# stm32n657.net
KiCad netlist of a schematic drawn in Altium Designer
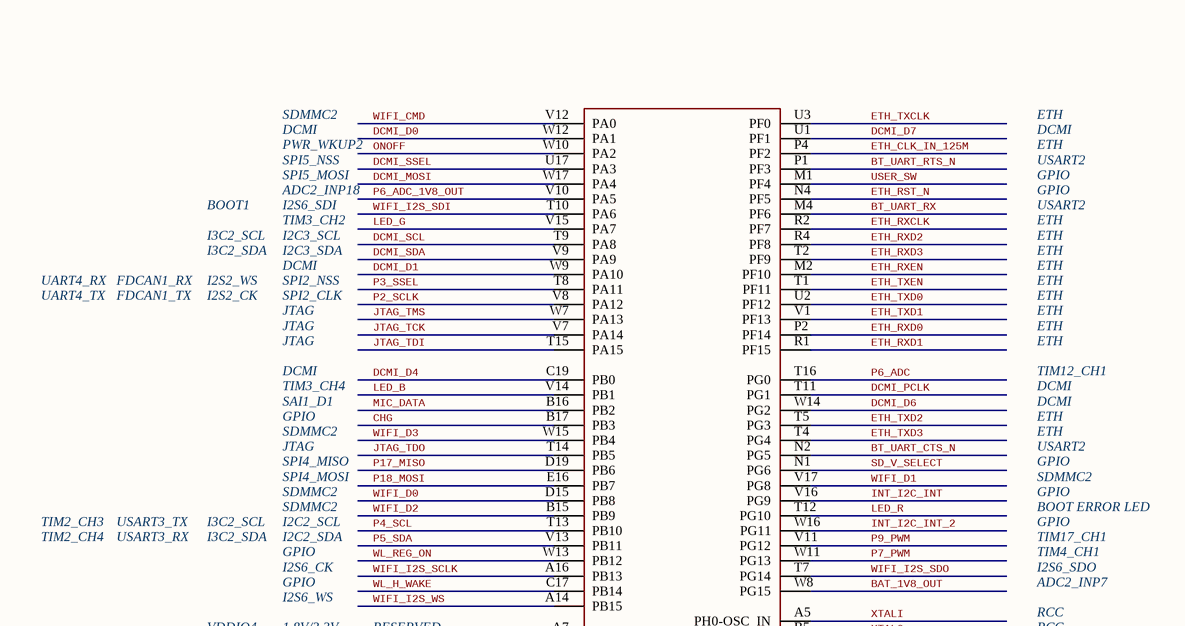
[diagram p0: stm32n657.SchDoc, top left]
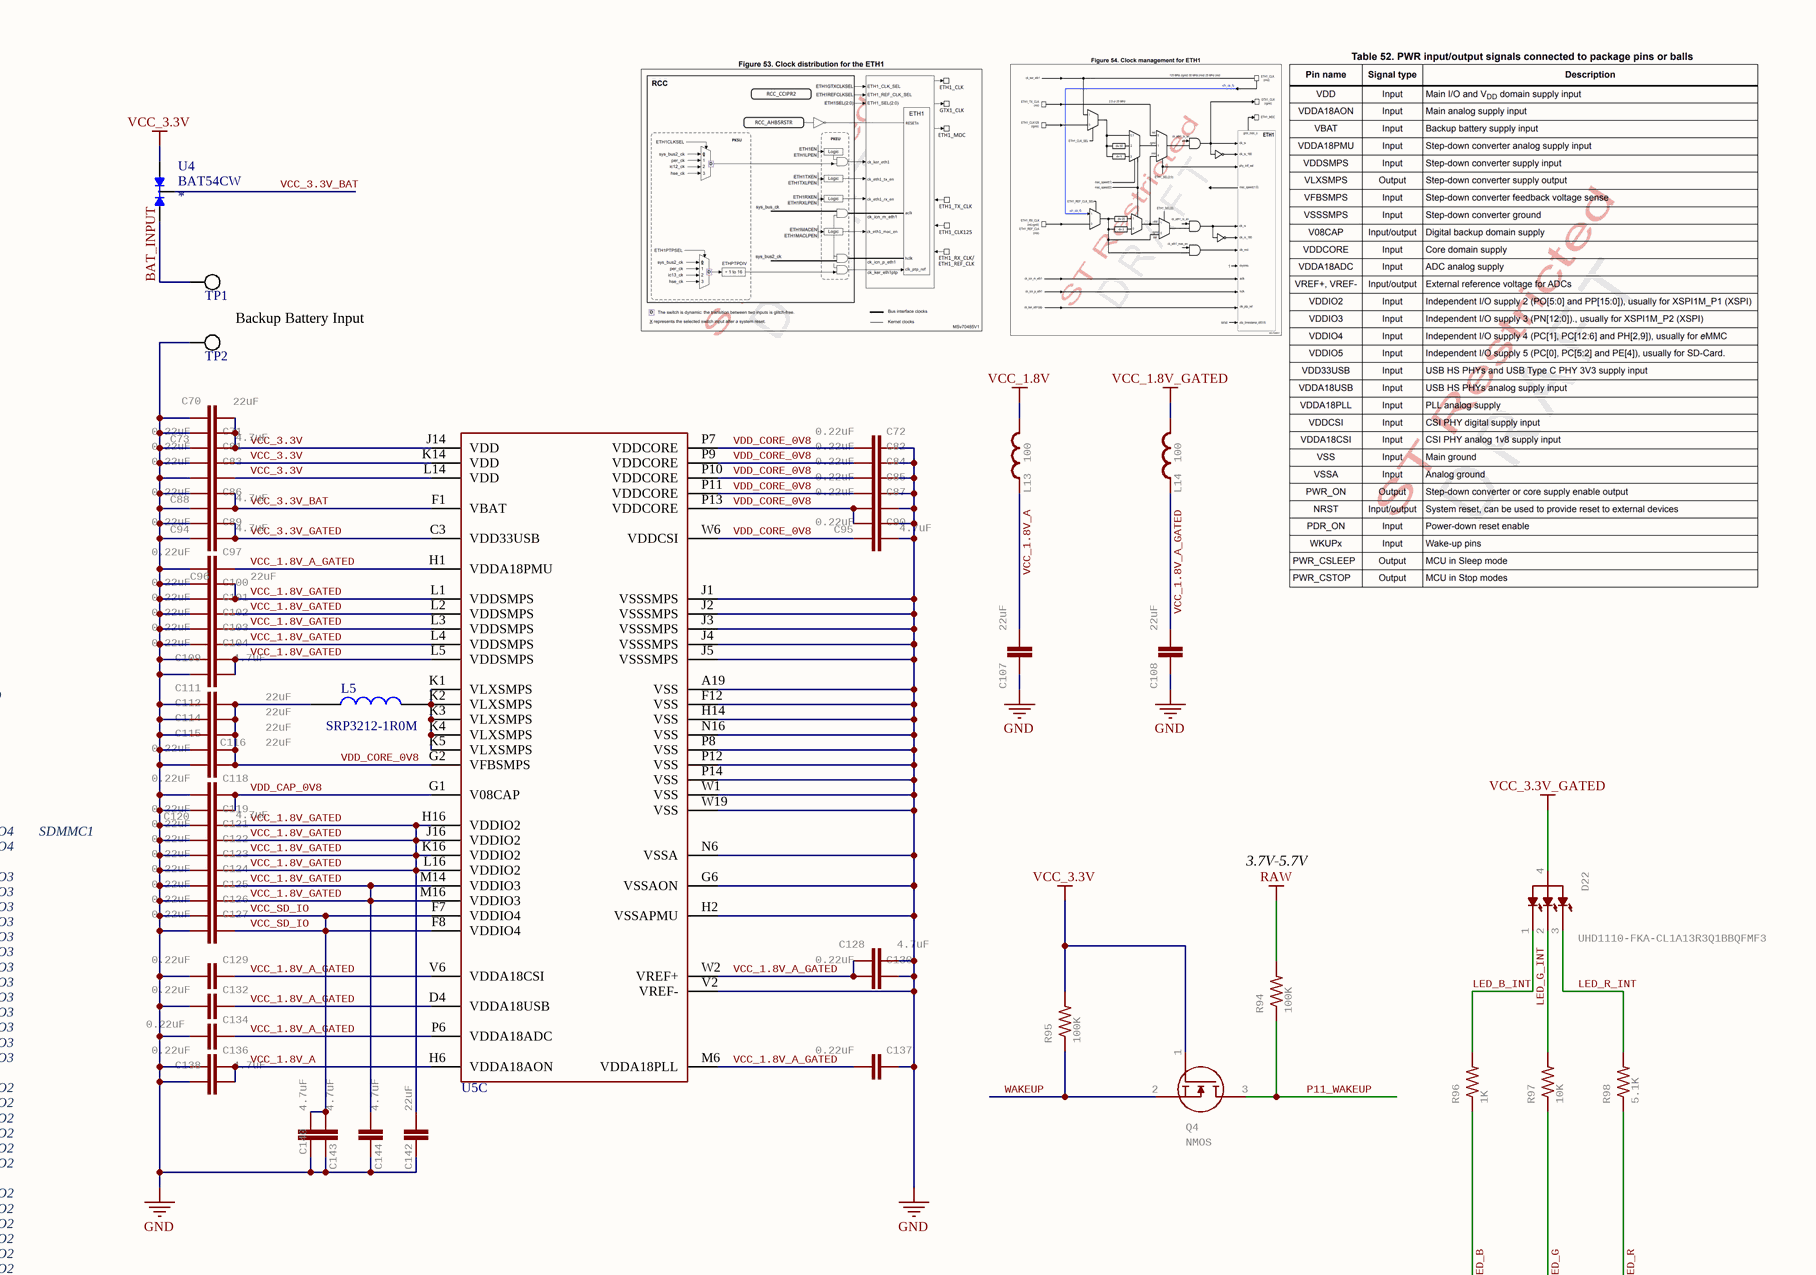
[diagram p1: stm32n657.SchDoc, top right]
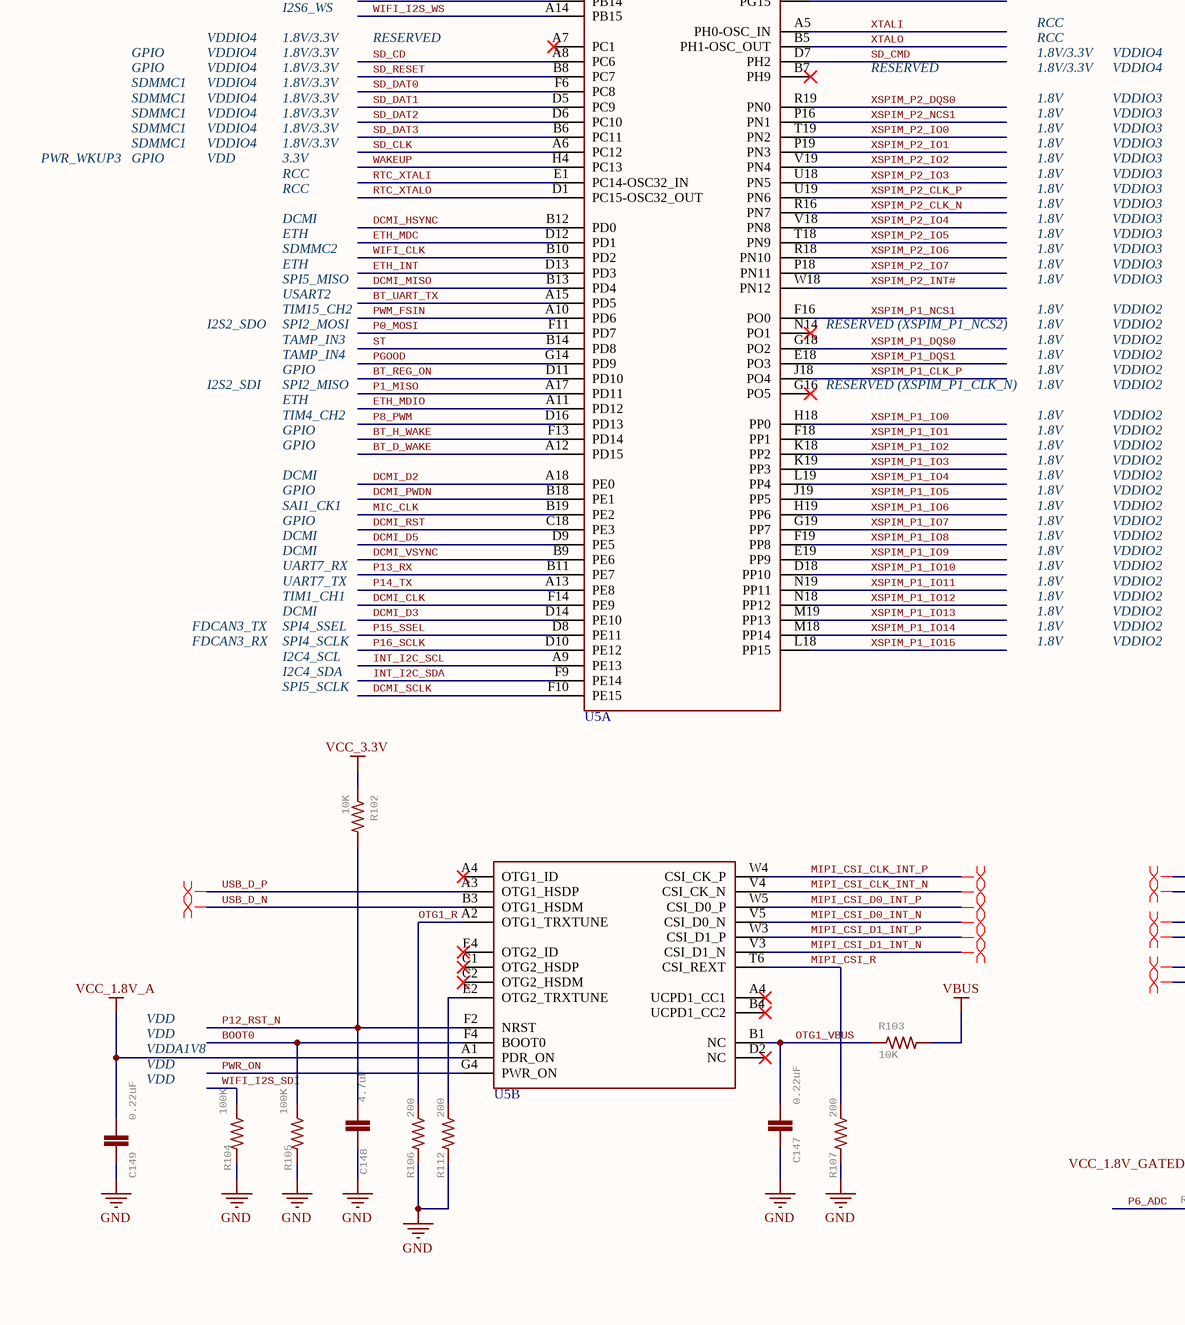
[diagram p2: stm32n657.SchDoc, bottom left]
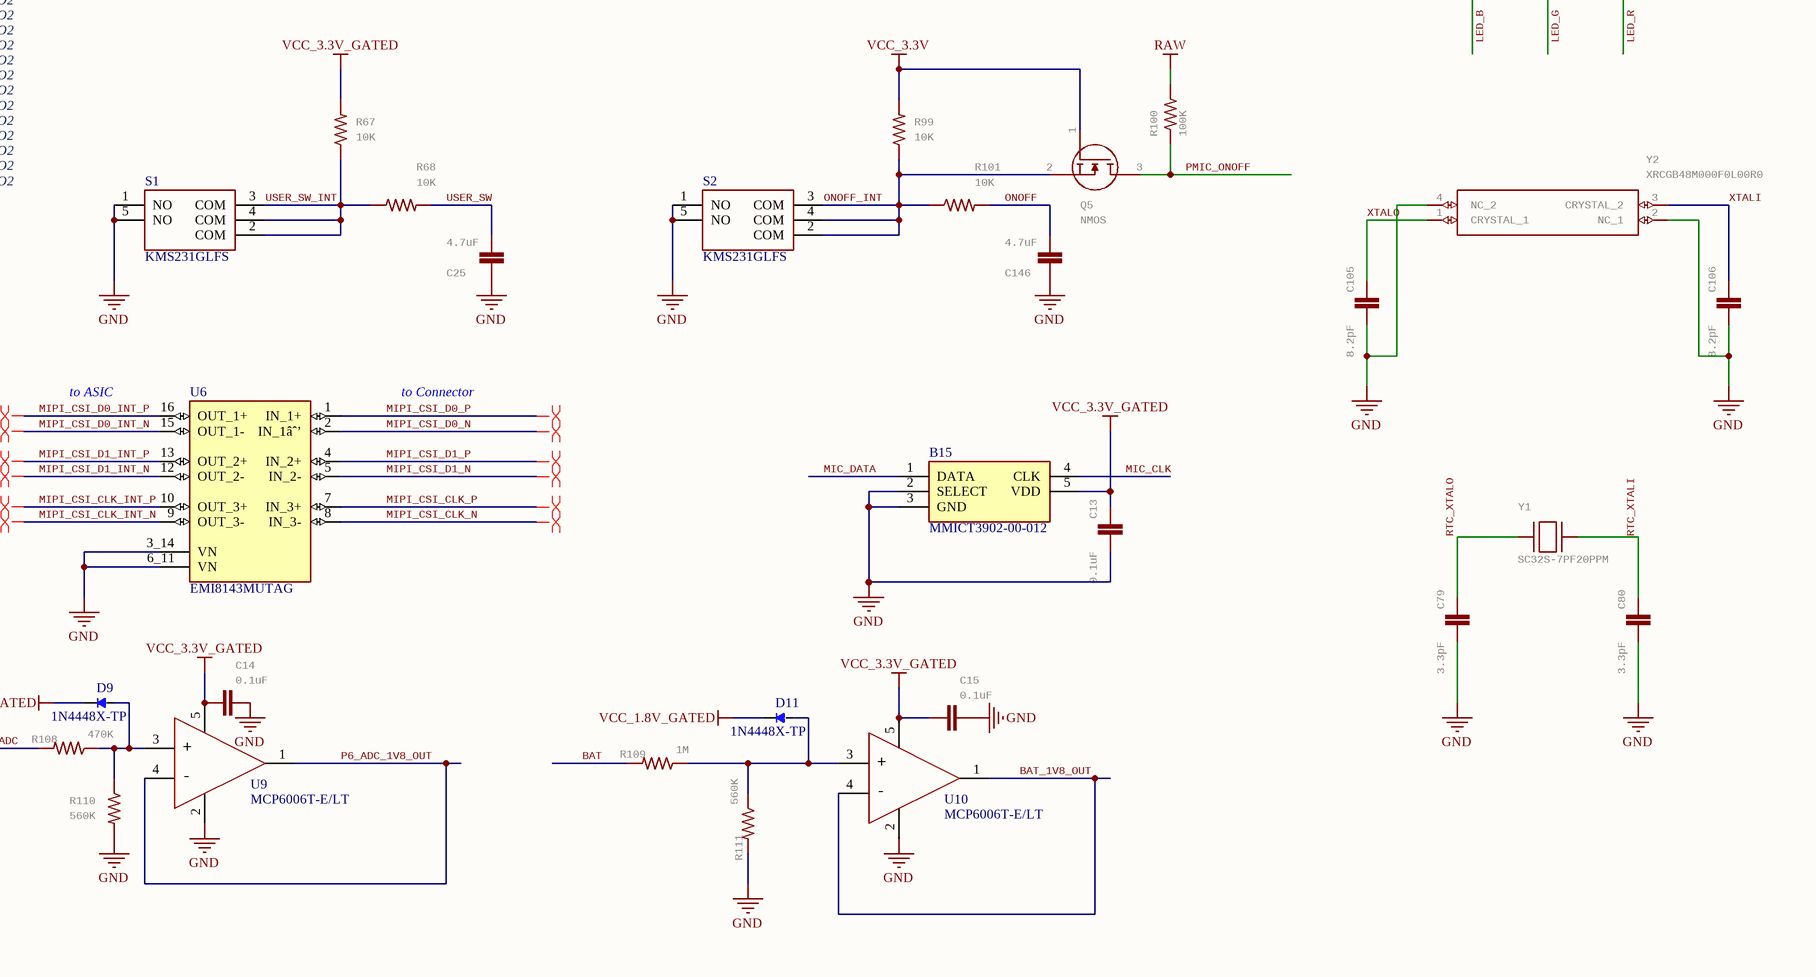
[diagram p3: stm32n657.SchDoc, bottom right]

(export (version "E")
  (design (tool "Eeschema 10.0.6"))
  (components
    (comp (ref "B15")
      (value "MMICT3902-00-012")
      (footprint "MMICT390200012")
      (description "Mic Omni-Directional -26dB Rectangle Solder Pad")
      (fields (field (name "MOUSER PART NUMBER") "410-MMICT3902-00-012"))
      (libsource (lib "MMICT3902-00-012") (part "MMICT3902-00-012"))
    )
    (comp (ref "C13")
      (value "0.1uF")
      (footprint "0402-CAP")
      (description "CAPACITOR, European symbol")
      (fields (field (name "MPN") "C0402C104Z4VAC"))
      (libsource (lib "") (part "C-EUC0201_1"))
    )
    (comp (ref "C14")
      (value "0.1uF")
      (footprint "0402-CAP")
      (description "CAPACITOR, European symbol")
      (fields (field (name "MPN") "C0402C104Z4VAC"))
      (libsource (lib "openmv-ae3") (part "C-EUC0201"))
    )
    (comp (ref "C15")
      (value "0.1uF")
      (footprint "0402-CAP")
      (description "CAPACITOR, European symbol")
      (fields (field (name "MPN") "C0402C104Z4VAC"))
      (libsource (lib "openmv-ae3") (part "C-EUC0201"))
    )
    (comp (ref "C25")
      (value "4.7uF")
      (footprint "0402-CAP")
      (description "CapacitorStandard 0603 ceramic capacitor, and 0.1\" leaded capacitor.")
      (fields (field (name "MPN") "JMK105BBJ475MV-F"))
      (libsource (lib "") (part "CAP0402-CAP_3"))
    )
    (comp (ref "C70")
      (value "22uF")
      (footprint "0805")
      (fields (field (name "MPN") "CL21A226MQQNNNE"))
      (libsource (lib "") (part "22UF-0805-6.3V-20%_1"))
    )
    (comp (ref "C71")
      (value "0.22uF")
      (footprint "C0201")
      (description "CAPACITOR, European symbol")
      (fields (field (name "MPN") "GRM033R60J224ME15D"))
      (libsource (lib "rt10") (part "C-EUC0201"))
    )
    (comp (ref "C72")
      (value "0.22uF")
      (footprint "C0201")
      (description "CAPACITOR, European symbol")
      (fields (field (name "MPN") "GRM033R60J224ME15D"))
      (libsource (lib "rt10") (part "C-EUC0201"))
    )
    (comp (ref "C73")
      (value "4.7uF")
      (footprint "0402-CAP")
      (description "CapacitorStandard 0603 ceramic capacitor, and 0.1\" leaded capacitor.")
      (fields (field (name "MPN") "JMK105BBJ475MV-F"))
      (libsource (lib "rt10") (part "CAP0402-CAP"))
    )
    (comp (ref "C79")
      (value "3.3pF")
      (footprint "C0201")
      (description "CAPACITOR, European symbol")
      (fields (field (name "MPN") "GRM0335C1H3R3CA01D"))
      (libsource (lib "") (part "C-EUC0201_1"))
    )
    (comp (ref "C80")
      (value "3.3pF")
      (footprint "C0201")
      (description "CAPACITOR, European symbol")
      (fields (field (name "MPN") "GRM0335C1H3R3CA01D"))
      (libsource (lib "") (part "C-EUC0201_1"))
    )
    (comp (ref "C81")
      (value "0.22uF")
      (footprint "C0201")
      (description "CAPACITOR, European symbol")
      (fields (field (name "MPN") "GRM033R60J224ME15D"))
      (libsource (lib "rt10") (part "C-EUC0201"))
    )
    (comp (ref "C82")
      (value "0.22uF")
      (footprint "C0201")
      (description "CAPACITOR, European symbol")
      (fields (field (name "MPN") "GRM033R60J224ME15D"))
      (libsource (lib "rt10") (part "C-EUC0201"))
    )
    (comp (ref "C83")
      (value "0.22uF")
      (footprint "C0201")
      (description "CAPACITOR, European symbol")
      (fields (field (name "MPN") "GRM033R60J224ME15D"))
      (libsource (lib "rt10") (part "C-EUC0201"))
    )
    (comp (ref "C84")
      (value "0.22uF")
      (footprint "C0201")
      (description "CAPACITOR, European symbol")
      (fields (field (name "MPN") "GRM033R60J224ME15D"))
      (libsource (lib "rt10") (part "C-EUC0201"))
    )
    (comp (ref "C85")
      (value "0.22uF")
      (footprint "C0201")
      (description "CAPACITOR, European symbol")
      (fields (field (name "MPN") "GRM033R60J224ME15D"))
      (libsource (lib "rt10") (part "C-EUC0201"))
    )
    (comp (ref "C86")
      (value "0.22uF")
      (footprint "C0201")
      (description "CAPACITOR, European symbol")
      (fields (field (name "MPN") "GRM033R60J224ME15D"))
      (libsource (lib "rt10") (part "C-EUC0201"))
    )
    (comp (ref "C87")
      (value "0.22uF")
      (footprint "C0201")
      (description "CAPACITOR, European symbol")
      (fields (field (name "MPN") "GRM033R60J224ME15D"))
      (libsource (lib "rt10") (part "C-EUC0201"))
    )
    (comp (ref "C88")
      (value "4.7uF")
      (footprint "0402-CAP")
      (description "CapacitorStandard 0603 ceramic capacitor, and 0.1\" leaded capacitor.")
      (fields (field (name "MPN") "JMK105BBJ475MV-F"))
      (libsource (lib "rt10") (part "CAP0402-CAP"))
    )
    (comp (ref "C89")
      (value "0.22uF")
      (footprint "C0201")
      (description "CAPACITOR, European symbol")
      (fields (field (name "MPN") "GRM033R60J224ME15D"))
      (libsource (lib "rt10") (part "C-EUC0201"))
    )
    (comp (ref "C90")
      (value "0.22uF")
      (footprint "C0201")
      (description "CAPACITOR, European symbol")
      (fields (field (name "MPN") "GRM033R60J224ME15D"))
      (libsource (lib "rt10") (part "C-EUC0201"))
    )
    (comp (ref "C94")
      (value "4.7uF")
      (footprint "0402-CAP")
      (description "CapacitorStandard 0603 ceramic capacitor, and 0.1\" leaded capacitor.")
      (fields (field (name "MPN") "JMK105BBJ475MV-F"))
      (libsource (lib "rt10") (part "CAP0402-CAP"))
    )
    (comp (ref "C95")
      (value "4.7uF")
      (footprint "0402-CAP")
      (description "CapacitorStandard 0603 ceramic capacitor, and 0.1\" leaded capacitor.")
      (fields (field (name "MPN") "JMK105BBJ475MV-F"))
      (libsource (lib "rt10") (part "CAP0402-CAP"))
    )
    (comp (ref "C96")
      (value "22uF")
      (footprint "0805")
      (fields (field (name "MPN") "CL21A226MQQNNNE"))
      (libsource (lib "") (part "22UF-0805-6.3V-20%_1"))
    )
    (comp (ref "C97")
      (value "0.22uF")
      (footprint "C0201")
      (description "CAPACITOR, European symbol")
      (fields (field (name "MPN") "GRM033R60J224ME15D"))
      (libsource (lib "rt10") (part "C-EUC0201"))
    )
    (comp (ref "C100")
      (value "0.22uF")
      (footprint "C0201")
      (description "CAPACITOR, European symbol")
      (fields (field (name "MPN") "GRM033R60J224ME15D"))
      (libsource (lib "rt10") (part "C-EUC0201"))
    )
    (comp (ref "C101")
      (value "0.22uF")
      (footprint "C0201")
      (description "CAPACITOR, European symbol")
      (fields (field (name "MPN") "GRM033R60J224ME15D"))
      (libsource (lib "rt10") (part "C-EUC0201"))
    )
    (comp (ref "C102")
      (value "0.22uF")
      (footprint "C0201")
      (description "CAPACITOR, European symbol")
      (fields (field (name "MPN") "GRM033R60J224ME15D"))
      (libsource (lib "rt10") (part "C-EUC0201"))
    )
    (comp (ref "C103")
      (value "0.22uF")
      (footprint "C0201")
      (description "CAPACITOR, European symbol")
      (fields (field (name "MPN") "GRM033R60J224ME15D"))
      (libsource (lib "rt10") (part "C-EUC0201"))
    )
    (comp (ref "C104")
      (value "0.22uF")
      (footprint "C0201")
      (description "CAPACITOR, European symbol")
      (fields (field (name "MPN") "GRM033R60J224ME15D"))
      (libsource (lib "rt10") (part "C-EUC0201"))
    )
    (comp (ref "C105")
      (value "8.2pF")
      (footprint "C0201")
      (description "CAPACITOR, European symbol")
      (fields (field (name "MPN") "GRM0335C1H8R2CA01D"))
      (libsource (lib "") (part "C-EUC0201_1"))
    )
    (comp (ref "C106")
      (value "8.2pF")
      (footprint "C0201")
      (description "CAPACITOR, European symbol")
      (fields (field (name "MPN") "GRM0335C1H8R2CA01D"))
      (libsource (lib "") (part "C-EUC0201_1"))
    )
    (comp (ref "C107")
      (value "22uF")
      (footprint "0805")
      (fields (field (name "MPN") "CL21A226MQQNNNE"))
      (libsource (lib "rt10") (part "22UF-0805-6.3V-20%"))
    )
    (comp (ref "C108")
      (value "22uF")
      (footprint "0805")
      (fields (field (name "MPN") "CL21A226MQQNNNE"))
      (libsource (lib "rt10") (part "22UF-0805-6.3V-20%"))
    )
    (comp (ref "C109")
      (value "4.7uF")
      (footprint "0402-CAP")
      (description "CapacitorStandard 0603 ceramic capacitor, and 0.1\" leaded capacitor.")
      (fields (field (name "MPN") "JMK105BBJ475MV-F"))
      (libsource (lib "") (part "CAP0402-CAP_1"))
    )
    (comp (ref "C111")
      (value "22uF")
      (footprint "0805")
      (fields (field (name "MPN") "CL21A226MQQNNNE"))
      (libsource (lib "") (part "22UF-0805-6.3V-20%_1"))
    )
    (comp (ref "C112")
      (value "22uF")
      (footprint "0805")
      (fields (field (name "MPN") "CL21A226MQQNNNE"))
      (libsource (lib "") (part "22UF-0805-6.3V-20%_1"))
    )
    (comp (ref "C114")
      (value "22uF")
      (footprint "0805")
      (fields (field (name "MPN") "CL21A226MQQNNNE"))
      (libsource (lib "") (part "22UF-0805-6.3V-20%_1"))
    )
    (comp (ref "C115")
      (value "22uF")
      (footprint "0805")
      (fields (field (name "MPN") "CL21A226MQQNNNE"))
      (libsource (lib "") (part "22UF-0805-6.3V-20%_1"))
    )
    (comp (ref "C116")
      (value "0.22uF")
      (footprint "C0201")
      (description "CAPACITOR, European symbol")
      (fields (field (name "MPN") "GRM033R60J224ME15D"))
      (libsource (lib "rt10") (part "C-EUC0201"))
    )
    (comp (ref "C118")
      (value "0.22uF")
      (footprint "C0201")
      (description "CAPACITOR, European symbol")
      (fields (field (name "MPN") "GRM033R60J224ME15D"))
      (libsource (lib "rt10") (part "C-EUC0201"))
    )
    (comp (ref "C119")
      (value "0.22uF")
      (footprint "C0201")
      (description "CAPACITOR, European symbol")
      (fields (field (name "MPN") "GRM033R60J224ME15D"))
      (libsource (lib "rt10") (part "C-EUC0201"))
    )
    (comp (ref "C120")
      (value "4.7uF")
      (footprint "0402-CAP")
      (description "CapacitorStandard 0603 ceramic capacitor, and 0.1\" leaded capacitor.")
      (fields (field (name "MPN") "JMK105BBJ475MV-F"))
      (libsource (lib "rt10") (part "CAP0402-CAP"))
    )
    (comp (ref "C121")
      (value "0.22uF")
      (footprint "C0201")
      (description "CAPACITOR, European symbol")
      (fields (field (name "MPN") "GRM033R60J224ME15D"))
      (libsource (lib "rt10") (part "C-EUC0201"))
    )
    (comp (ref "C122")
      (value "0.22uF")
      (footprint "C0201")
      (description "CAPACITOR, European symbol")
      (fields (field (name "MPN") "GRM033R60J224ME15D"))
      (libsource (lib "rt10") (part "C-EUC0201"))
    )
    (comp (ref "C123")
      (value "0.22uF")
      (footprint "C0201")
      (description "CAPACITOR, European symbol")
      (fields (field (name "MPN") "GRM033R60J224ME15D"))
      (libsource (lib "rt10") (part "C-EUC0201"))
    )
    (comp (ref "C124")
      (value "0.22uF")
      (footprint "C0201")
      (description "CAPACITOR, European symbol")
      (fields (field (name "MPN") "GRM033R60J224ME15D"))
      (libsource (lib "rt10") (part "C-EUC0201"))
    )
    (comp (ref "C125")
      (value "0.22uF")
      (footprint "C0201")
      (description "CAPACITOR, European symbol")
      (fields (field (name "MPN") "GRM033R60J224ME15D"))
      (libsource (lib "rt10") (part "C-EUC0201"))
    )
    (comp (ref "C126")
      (value "0.22uF")
      (footprint "C0201")
      (description "CAPACITOR, European symbol")
      (fields (field (name "MPN") "GRM033R60J224ME15D"))
      (libsource (lib "rt10") (part "C-EUC0201"))
    )
    (comp (ref "C127")
      (value "0.22uF")
      (footprint "C0201")
      (description "CAPACITOR, European symbol")
      (fields (field (name "MPN") "GRM033R60J224ME15D"))
      (libsource (lib "rt10") (part "C-EUC0201"))
    )
    (comp (ref "C128")
      (value "4.7uF")
      (footprint "0402-CAP")
      (description "CapacitorStandard 0603 ceramic capacitor, and 0.1\" leaded capacitor.")
      (fields (field (name "MPN") "JMK105BBJ475MV-F"))
      (libsource (lib "") (part "CAP0402-CAP_1"))
    )
    (comp (ref "C129")
      (value "0.22uF")
      (footprint "C0201")
      (description "CAPACITOR, European symbol")
      (fields (field (name "MPN") "GRM033R60J224ME15D"))
      (libsource (lib "rt10") (part "C-EUC0201"))
    )
    (comp (ref "C130")
      (value "0.22uF")
      (footprint "C0201")
      (description "CAPACITOR, European symbol")
      (fields (field (name "MPN") "GRM033R60J224ME15D"))
      (libsource (lib "rt10") (part "C-EUC0201"))
    )
    (comp (ref "C132")
      (value "0.22uF")
      (footprint "C0201")
      (description "CAPACITOR, European symbol")
      (fields (field (name "MPN") "GRM033R60J224ME15D"))
      (libsource (lib "rt10") (part "C-EUC0201"))
    )
    (comp (ref "C134")
      (value "0.22uF")
      (footprint "C0201")
      (description "CAPACITOR, European symbol")
      (fields (field (name "MPN") "GRM033R60J224ME15D"))
      (libsource (lib "rt10") (part "C-EUC0201"))
    )
    (comp (ref "C136")
      (value "0.22uF")
      (footprint "C0201")
      (description "CAPACITOR, European symbol")
      (fields (field (name "MPN") "GRM033R60J224ME15D"))
      (libsource (lib "rt10") (part "C-EUC0201"))
    )
    (comp (ref "C137")
      (value "0.22uF")
      (footprint "C0201")
      (description "CAPACITOR, European symbol")
      (fields (field (name "MPN") "GRM033R60J224ME15D"))
      (libsource (lib "rt10") (part "C-EUC0201"))
    )
    (comp (ref "C138")
      (value "4.7uF")
      (footprint "0402-CAP")
      (description "CapacitorStandard 0603 ceramic capacitor, and 0.1\" leaded capacitor.")
      (fields (field (name "MPN") "JMK105BBJ475MV-F"))
      (libsource (lib "") (part "CAP0402-CAP_1"))
    )
    (comp (ref "C140")
      (value "4.7uF")
      (footprint "0402-CAP")
      (description "CapacitorStandard 0603 ceramic capacitor, and 0.1\" leaded capacitor.")
      (fields (field (name "MPN") "JMK105BBJ475MV-F"))
      (libsource (lib "") (part "CAP0402-CAP_2"))
    )
    (comp (ref "C142")
      (value "22uF")
      (footprint "0805")
      (fields (field (name "MPN") "CL21A226MQQNNNE"))
      (libsource (lib "rt10") (part "22UF-0805-6.3V-20%"))
    )
    (comp (ref "C143")
      (value "4.7uF")
      (footprint "0402-CAP")
      (description "CapacitorStandard 0603 ceramic capacitor, and 0.1\" leaded capacitor.")
      (fields (field (name "MPN") "JMK105BBJ475MV-F"))
      (libsource (lib "") (part "CAP0402-CAP_2"))
    )
    (comp (ref "C144")
      (value "4.7uF")
      (footprint "0402-CAP")
      (description "CapacitorStandard 0603 ceramic capacitor, and 0.1\" leaded capacitor.")
      (fields (field (name "MPN") "JMK105BBJ475MV-F"))
      (libsource (lib "") (part "CAP0402-CAP_2"))
    )
    (comp (ref "C146")
      (value "4.7uF")
      (footprint "0402-CAP")
      (description "CapacitorStandard 0603 ceramic capacitor, and 0.1\" leaded capacitor.")
      (fields (field (name "MPN") "JMK105BBJ475MV-F"))
      (libsource (lib "") (part "CAP0402-CAP_3"))
    )
    (comp (ref "C147")
      (value "0.22uF")
      (footprint "C0201")
      (description "CAPACITOR, European symbol")
      (fields (field (name "MPN") "GRM033R60J224ME15D"))
      (libsource (lib "") (part "C-EUC0201_2"))
    )
    (comp (ref "C148")
      (value "4.7uF")
      (footprint "0402-CAP")
      (description "CapacitorStandard 0603 ceramic capacitor, and 0.1\" leaded capacitor.")
      (fields (field (name "MPN") "JMK105BBJ475MV-F"))
      (libsource (lib "") (part "CAP0402-CAP_2"))
    )
    (comp (ref "C149")
      (value "0.22uF")
      (footprint "C0201")
      (description "CAPACITOR, European symbol")
      (fields (field (name "MPN") "GRM033R60J224ME15D"))
      (libsource (lib "") (part "C-EUC0201_2"))
    )
    (comp (ref "D9")
      (value "DIODE_GP")
      (footprint "SOD523")
      (fields (field (name "MPN") "1N4448X-TP"))
      (libsource (lib "openmv-n6") (part "DIODE_GP"))
    )
    (comp (ref "D11")
      (value "DIODE_GP")
      (footprint "SOD523")
      (fields (field (name "MPN") "1N4448X-TP"))
      (libsource (lib "openmv-n6") (part "DIODE_GP"))
    )
    (comp (ref "D22")
      (value "UHD1110-FKA-CL1A13R3Q1BBQFMF3")
      (footprint "LED_UHD1110-FKA-CL1A13R3Q1BBQFMF3")
      (description "LED RGB SMD, SIZE 1 X 1 mm Check availability")
      (fields (field (name "MF") "Cree Inc.") (field (name "MPN") "UHD1110-FKA-CL1A13r3q1BBQFMF3"))
      (libsource (lib "rt10") (part "UHD1110-FKA-CL1A13R3Q1BBQFMF3"))
    )
    (comp (ref "L5")
      (value "SRP3212-1R0M")
      (footprint "IND3225X100N")
      (description "Ind,3.2x2.5x1mm,1.0uH?20%,6.5A,shd")
      (fields (field (name "MOUSER PART NUMBER") "652-SRP3212-1R0M"))
      (libsource (lib "openmv-ae3") (part "SRP3212-2R2M"))
    )
    (comp (ref "L13")
      (value "100")
      (footprint "C0402")
      (fields (field (name "MPN") "MFBM1V1005-101-R"))
      (libsource (lib "rt10") (part "INDUCTOR0402"))
    )
    (comp (ref "L14")
      (value "100")
      (footprint "C0402")
      (fields (field (name "MPN") "MFBM1V1005-101-R"))
      (libsource (lib "rt10") (part "INDUCTOR0402"))
    )
    (comp (ref "Q4")
      (value "NMOS")
      (footprint "DFN1006")
      (description "MOSFET 60V N-Channel Enhancement Mode MOSFET - ESD Protected   Source:  Datasheet")
      (libsource (lib "rt10") (part "2N7002KW_R1_00001"))
    )
    (comp (ref "Q5")
      (value "NMOS")
      (footprint "DFN1006")
      (description "MOSFET 60V N-Channel Enhancement Mode MOSFET - ESD Protected   Source:  Datasheet")
      (libsource (lib "rt10") (part "2N7002KW_R1_00001"))
    )
    (comp (ref "R67")
      (value "10K")
      (footprint "0402-RES")
      (description "ResistorBasic schematic elements and footprints for 0603, 1206, and PTH resistors.")
      (fields (field (name "MPN") "AC0402FR-1310K"))
      (libsource (lib "rt10") (part "RESISTOR0402-RES"))
    )
    (comp (ref "R68")
      (value "10K")
      (footprint "0402-RES")
      (description "ResistorBasic schematic elements and footprints for 0603, 1206, and PTH resistors.")
      (fields (field (name "MPN") "AC0402FR-1310K"))
      (libsource (lib "rt10") (part "RESISTOR0402-RES"))
    )
    (comp (ref "R94")
      (value "100K")
      (footprint "0402-RES")
      (description "ResistorBasic schematic elements and footprints for 0603, 1206, and PTH resistors.")
      (fields (field (name "MPN") "AC0402FR-07100KL"))
      (libsource (lib "rt10") (part "RESISTOR0402-RES"))
    )
    (comp (ref "R95")
      (value "100K")
      (footprint "0402-RES")
      (description "ResistorBasic schematic elements and footprints for 0603, 1206, and PTH resistors.")
      (fields (field (name "MPN") "AC0402FR-07100KL"))
      (libsource (lib "rt10") (part "RESISTOR0402-RES"))
    )
    (comp (ref "R96")
      (value "1K")
      (footprint "0402-RES")
      (description "ResistorBasic schematic elements and footprints for 0603, 1206, and PTH resistors.")
      (fields (field (name "MPN") "CRCW04021K00FKEDC"))
      (libsource (lib "rt10") (part "RESISTOR0402-RES"))
    )
    (comp (ref "R97")
      (value "10K")
      (footprint "0402-RES")
      (description "ResistorBasic schematic elements and footprints for 0603, 1206, and PTH resistors.")
      (fields (field (name "MPN") "AC0402FR-1310KL"))
      (libsource (lib "rt10") (part "RESISTOR0402-RES"))
    )
    (comp (ref "R98")
      (value "5.1K")
      (footprint "0402-RES")
      (description "ResistorBasic schematic elements and footprints for 0603, 1206, and PTH resistors.")
      (fields (field (name "MPN") "RC0402JR-075K1L"))
      (libsource (lib "rt10") (part "RESISTOR0402-RES"))
    )
    (comp (ref "R99")
      (value "10K")
      (footprint "0402-RES")
      (description "ResistorBasic schematic elements and footprints for 0603, 1206, and PTH resistors.")
      (fields (field (name "MPN") "AC0402FR-1310K"))
      (libsource (lib "rt10") (part "RESISTOR0402-RES"))
    )
    (comp (ref "R100")
      (value "100K")
      (footprint "0402-RES")
      (description "ResistorBasic schematic elements and footprints for 0603, 1206, and PTH resistors.")
      (fields (field (name "MPN") "AC0402FR-07100KL"))
      (libsource (lib "rt10") (part "RESISTOR0402-RES"))
    )
    (comp (ref "R101")
      (value "10K")
      (footprint "0402-RES")
      (description "ResistorBasic schematic elements and footprints for 0603, 1206, and PTH resistors.")
      (fields (field (name "MPN") "AC0402FR-1310K"))
      (libsource (lib "rt10") (part "RESISTOR0402-RES"))
    )
    (comp (ref "R102")
      (value "10K")
      (footprint "0402-RES")
      (description "ResistorBasic schematic elements and footprints for 0603, 1206, and PTH resistors.")
      (fields (field (name "MPN") "AC0402FR-1310KL"))
      (libsource (lib "rt10") (part "RESISTOR0402-RES"))
    )
    (comp (ref "R103")
      (value "10K")
      (footprint "0402-RES")
      (description "ResistorBasic schematic elements and footprints for 0603, 1206, and PTH resistors.")
      (fields (field (name "MPN") "AC0402FR-1310KL"))
      (libsource (lib "rt10") (part "RESISTOR0402-RES"))
    )
    (comp (ref "R104")
      (value "100K")
      (footprint "0402-RES")
      (description "ResistorBasic schematic elements and footprints for 0603, 1206, and PTH resistors.")
      (fields (field (name "MPN") "AC0402FR-07100KL"))
      (libsource (lib "openmv-ae3") (part "RESISTOR0402-RES"))
    )
    (comp (ref "R105")
      (value "100K")
      (footprint "0402-RES")
      (description "ResistorBasic schematic elements and footprints for 0603, 1206, and PTH resistors.")
      (fields (field (name "MPN") "AC0402FR-07100KL"))
      (libsource (lib "openmv-ae3") (part "RESISTOR0402-RES"))
    )
    (comp (ref "R106")
      (value "200")
      (footprint "R0201")
      (fields (field (name "MPN") "CR0201-FW-2000GLF"))
      (libsource (lib "openmv-ae3") (part "RESISTOR0402-RES"))
    )
    (comp (ref "R107")
      (value "200")
      (footprint "R0201")
      (fields (field (name "MPN") "CR0201-FW-2000GLF"))
      (libsource (lib "openmv-ae3") (part "RESISTOR0402-RES"))
    )
    (comp (ref "R108")
      (value "470K")
      (footprint "0402-RES")
      (description "ResistorBasic schematic elements and footprints for 0603, 1206, and PTH resistors.")
      (fields (field (name "MPN") "RC0402FR-7D470KL"))
      (libsource (lib "openmv-ae3") (part "RESISTOR0402-RES"))
    )
    (comp (ref "R109")
      (value "1M")
      (footprint "0402-RES")
      (description "ResistorBasic schematic elements and footprints for 0603, 1206, and PTH resistors.")
      (fields (field (name "MPN") "CRCW04021M00FKEDC"))
      (libsource (lib "openmv-ae3") (part "RESISTOR0402-RES"))
    )
    (comp (ref "R110")
      (value "560K")
      (footprint "0402-RES")
      (description "ResistorBasic schematic elements and footprints for 0603, 1206, and PTH resistors.")
      (fields (field (name "MPN") "RMCF0402FT560K"))
      (libsource (lib "openmv-ae3") (part "RESISTOR0402-RES"))
    )
    (comp (ref "R111")
      (value "560K")
      (footprint "0402-RES")
      (description "ResistorBasic schematic elements and footprints for 0603, 1206, and PTH resistors.")
      (fields (field (name "MPN") "RMCF0402FT560K"))
      (libsource (lib "openmv-ae3") (part "RESISTOR0402-RES"))
    )
    (comp (ref "R112")
      (value "200")
      (footprint "R0201")
      (fields (field (name "MPN") "CR0201-FW-2000GLF"))
      (libsource (lib "openmv-ae3") (part "RESISTOR0402-RES"))
    )
    (comp (ref "S1")
      (value "KMS231GLFS")
      (footprint "KMS231GLFS")
      (libsource (lib "rt10") (part "KMS231GLFS"))
    )
    (comp (ref "S2")
      (value "KMS231GLFS")
      (footprint "KMS231GLFS")
      (libsource (lib "rt10") (part "KMS231GLFS"))
    )
    (comp (ref "TP1") (value "TP") (footprint "TP_1p8") (libsource (lib "rt10") (part "TP")))
    (comp (ref "TP2") (value "TP") (footprint "TP_1p8") (libsource (lib "rt10") (part "TP")))
    (comp (ref "U4")
      (value "BAT54CW")
      (footprint "SOT65P210X110-3N")
      (description "Diode Array 1 Pair Common Cathode Schottky 30 V 200mA (DC) Surface Mount SC-70, SOT-323")
      (fields
        (field (name "MF") "ON Semiconductor")
        (field (name "PART NUMBER") "BAT54CW,115")
        (field (name "ALTIUM_VALUE") "*")
      )
      (libsource (lib "stm32n657") (part "BAT54CW"))
    )
    (comp (ref "U5")
      (value "STM32N657_223")
      (footprint "STM32N657_VFBGA223")
      (fields (field (name "MPN") "STM32N657"))
      (libsource (lib "stm32n657") (part "STM32N657_223"))
    )
    (comp (ref "U6")
      (value "EMI8143MUTAG")
      (footprint "IC_EMI8143MUTAG")
      (description "6 Line Common Mode Choke Surface Mount 100mA DCR 6Ohm (Typ)")
      (fields
        (field (name "MF") "ON Semiconductor")
        (field (name "DIGI-KEY_PART_NUMBER") "EMI8143MUTAGOSCT-ND")
      )
      (libsource (lib "openmv-ae3") (part "CMP-008-000000-1"))
    )
    (comp (ref "U9")
      (value "MCP6006T-E/LT")
      (footprint "SC70-5")
      (fields (field (name "MF") "Microchip"))
      (libsource (lib "openmv-n6") (part "MCP6006T-E/LT"))
    )
    (comp (ref "U10")
      (value "MCP6006T-E/LT")
      (footprint "SC70-5")
      (fields (field (name "MF") "Microchip"))
      (libsource (lib "openmv-n6") (part "MCP6006T-E/LT"))
    )
    (comp (ref "Y1")
      (value "SC32S-7PF20PPM")
      (footprint "XTAL_ABS07-32.768KHZ-7-T")
      (description "Check availability")
      (fields (field (name "MF") "Abracon") (field (name "MP") "ABS07-32.768KHZ-7-T"))
      (libsource (lib "rt10") (part "ABS07-32.768KHZ-7-T"))
    )
    (comp (ref "Y2")
      (value "XRCGB48M000F0L00R0")
      (footprint "XRCGB24M000F3M00R0")
      (description "Murata 48MHz Crystal +/-30ppm SMD 4-Pin 2 x 1.6 x 0.7mm   Source:  Datasheet")
      (fields (field (name "MOUSER_PART_NUMBER") "81-XRCGB48M000F0L00R0"))
      (libsource (lib "rt10") (part "XRCGB24M000F3M00R0"))
    )
  )
  (nets
    (net (code "1") (name "/BAT") (class "Default")
      (node (ref "R109") (pin "2") (pinfunction "2_2") (pintype "passive"))
    )
    (net (code "2") (name "/BAT_1V8_OUT") (class "Default")
      (node (ref "U10") (pin "1") (pinfunction "OUT_1") (pintype "passive"))
      (node (ref "U10") (pin "4") (pinfunction "IN-_4") (pintype "passive"))
      (node (ref "U5") (pin "W8") (pinfunction "PG15_W8") (pintype "passive"))
    )
    (net (code "3") (name "/BAT_INPUT") (class "Default")
      (node (ref "TP1") (pin "1") (pinfunction "1_1") (pintype "passive"))
      (node (ref "U4") (pin "2") (pinfunction "2_2") (pintype "passive"))
    )
    (net (code "4") (name "/BOOT0") (class "Default")
      (node (ref "R105") (pin "1") (pinfunction "1_1") (pintype "passive"))
      (node (ref "U5") (pin "F4") (pinfunction "BOOT0_F4") (pintype "passive"))
    )
    (net (code "5") (name "/BT_D_WAKE") (class "Default")
      (node (ref "U5") (pin "A12") (pinfunction "PD15_A12") (pintype "passive"))
    )
    (net (code "6") (name "/BT_H_WAKE") (class "Default")
      (node (ref "U5") (pin "F13") (pinfunction "PD14_F13") (pintype "passive"))
    )
    (net (code "7") (name "/BT_REG_ON") (class "Default")
      (node (ref "U5") (pin "D11") (pinfunction "PD10_D11") (pintype "passive"))
    )
    (net (code "8") (name "/BT_UART_CTS_N") (class "Default")
      (node (ref "U5") (pin "N2") (pinfunction "PG5_N2") (pintype "passive"))
    )
    (net (code "9") (name "/BT_UART_RTS_N") (class "Default")
      (node (ref "U5") (pin "P1") (pinfunction "PF3_P1") (pintype "passive"))
    )
    (net (code "10") (name "/BT_UART_RX") (class "Default")
      (node (ref "U5") (pin "M4") (pinfunction "PF6_M4") (pintype "passive"))
    )
    (net (code "11") (name "/BT_UART_TX") (class "Default")
      (node (ref "U5") (pin "A15") (pinfunction "PD5_A15") (pintype "passive"))
    )
    (net (code "12") (name "/CHG") (class "Default")
      (node (ref "U5") (pin "B17") (pinfunction "PB3_B17") (pintype "passive"))
    )
    (net (code "13") (name "/DCMI_CLK") (class "Default")
      (node (ref "U5") (pin "F14") (pinfunction "PE9_F14") (pintype "passive"))
    )
    (net (code "14") (name "/DCMI_D0") (class "Default")
      (node (ref "U5") (pin "W12") (pinfunction "PA1_W12") (pintype "passive"))
    )
    (net (code "15") (name "/DCMI_D1") (class "Default")
      (node (ref "U5") (pin "W9") (pinfunction "PA10_W9") (pintype "passive"))
    )
    (net (code "16") (name "/DCMI_D2") (class "Default")
      (node (ref "U5") (pin "A18") (pinfunction "PE0_A18") (pintype "passive"))
    )
    (net (code "17") (name "/DCMI_D3") (class "Default")
      (node (ref "U5") (pin "D14") (pinfunction "PE10_D14") (pintype "passive"))
    )
    (net (code "18") (name "/DCMI_D4") (class "Default")
      (node (ref "U5") (pin "C19") (pinfunction "PB0_C19") (pintype "passive"))
    )
    (net (code "19") (name "/DCMI_D5") (class "Default")
      (node (ref "U5") (pin "D9") (pinfunction "PE5_D9") (pintype "passive"))
    )
    (net (code "20") (name "/DCMI_D6") (class "Default")
      (node (ref "U5") (pin "W14") (pinfunction "PG2_W14") (pintype "passive"))
    )
    (net (code "21") (name "/DCMI_D7") (class "Default")
      (node (ref "U5") (pin "U1") (pinfunction "PF1_U1") (pintype "passive"))
    )
    (net (code "22") (name "/DCMI_HSYNC") (class "Default")
      (node (ref "U5") (pin "B12") (pinfunction "PD0_B12") (pintype "passive"))
    )
    (net (code "23") (name "/DCMI_MISO") (class "Default")
      (node (ref "U5") (pin "B13") (pinfunction "PD4_B13") (pintype "passive"))
    )
    (net (code "24") (name "/DCMI_MOSI") (class "Default")
      (node (ref "U5") (pin "W17") (pinfunction "PA4_W17") (pintype "passive"))
    )
    (net (code "25") (name "/DCMI_PCLK") (class "Default")
      (node (ref "U5") (pin "T11") (pinfunction "PG1_T11") (pintype "passive"))
    )
    (net (code "26") (name "/DCMI_PWDN") (class "Default")
      (node (ref "U5") (pin "B18") (pinfunction "PE1_B18") (pintype "passive"))
    )
    (net (code "27") (name "/DCMI_RST") (class "Default")
      (node (ref "U5") (pin "C18") (pinfunction "PE3_C18") (pintype "passive"))
    )
    (net (code "28") (name "/DCMI_SCL") (class "Default")
      (node (ref "U5") (pin "T9") (pinfunction "PA8_T9") (pintype "passive"))
    )
    (net (code "29") (name "/DCMI_SCLK") (class "Default")
      (node (ref "U5") (pin "F10") (pinfunction "PE15_F10") (pintype "passive"))
    )
    (net (code "30") (name "/DCMI_SDA") (class "Default")
      (node (ref "U5") (pin "V9") (pinfunction "PA9_V9") (pintype "passive"))
    )
    (net (code "31") (name "/DCMI_SSEL") (class "Default")
      (node (ref "U5") (pin "U17") (pinfunction "PA3_U17") (pintype "passive"))
    )
    (net (code "32") (name "/DCMI_VSYNC") (class "Default")
      (node (ref "U5") (pin "B9") (pinfunction "PE6_B9") (pintype "passive"))
    )
    (net (code "33") (name "/ETH_CLK_IN_125M") (class "Default")
      (node (ref "U5") (pin "P4") (pinfunction "PF2_P4") (pintype "passive"))
    )
    (net (code "34") (name "/ETH_INT") (class "Default")
      (node (ref "U5") (pin "D13") (pinfunction "PD3_D13") (pintype "passive"))
    )
    (net (code "35") (name "/ETH_MDC") (class "Default")
      (node (ref "U5") (pin "D12") (pinfunction "PD1_D12") (pintype "passive"))
    )
    (net (code "36") (name "/ETH_MDIO") (class "Default")
      (node (ref "U5") (pin "A11") (pinfunction "PD12_A11") (pintype "passive"))
    )
    (net (code "37") (name "/ETH_RST_N") (class "Default")
      (node (ref "U5") (pin "N4") (pinfunction "PF5_N4") (pintype "passive"))
    )
    (net (code "38") (name "/ETH_RXCLK") (class "Default")
      (node (ref "U5") (pin "R2") (pinfunction "PF7_R2") (pintype "passive"))
    )
    (net (code "39") (name "/ETH_RXD0") (class "Default")
      (node (ref "U5") (pin "P2") (pinfunction "PF14_P2") (pintype "passive"))
    )
    (net (code "40") (name "/ETH_RXD1") (class "Default")
      (node (ref "U5") (pin "R1") (pinfunction "PF15_R1") (pintype "passive"))
    )
    (net (code "41") (name "/ETH_RXD2") (class "Default")
      (node (ref "U5") (pin "R4") (pinfunction "PF8_R4") (pintype "passive"))
    )
    (net (code "42") (name "/ETH_RXD3") (class "Default")
      (node (ref "U5") (pin "T2") (pinfunction "PF9_T2") (pintype "passive"))
    )
    (net (code "43") (name "/ETH_RXEN") (class "Default")
      (node (ref "U5") (pin "M2") (pinfunction "PF10_M2") (pintype "passive"))
    )
    (net (code "44") (name "/ETH_TXCLK") (class "Default")
      (node (ref "U5") (pin "U3") (pinfunction "PF0_U3") (pintype "passive"))
    )
    (net (code "45") (name "/ETH_TXD0") (class "Default")
      (node (ref "U5") (pin "U2") (pinfunction "PF12_U2") (pintype "passive"))
    )
    (net (code "46") (name "/ETH_TXD1") (class "Default")
      (node (ref "U5") (pin "V1") (pinfunction "PF13_V1") (pintype "passive"))
    )
    (net (code "47") (name "/ETH_TXD2") (class "Default")
      (node (ref "U5") (pin "T5") (pinfunction "PG3_T5") (pintype "passive"))
    )
    (net (code "48") (name "/ETH_TXD3") (class "Default")
      (node (ref "U5") (pin "T4") (pinfunction "PG4_T4") (pintype "passive"))
    )
    (net (code "49") (name "/ETH_TXEN") (class "Default")
      (node (ref "U5") (pin "T1") (pinfunction "PF11_T1") (pintype "passive"))
    )
    (net (code "50") (name "/INT_I2C_INT") (class "Default")
      (node (ref "U5") (pin "V16") (pinfunction "PG9_V16") (pintype "passive"))
    )
    (net (code "51") (name "/INT_I2C_INT_2") (class "Default")
      (node (ref "U5") (pin "W16") (pinfunction "PG11_W16") (pintype "passive"))
    )
    (net (code "52") (name "/INT_I2C_SCL") (class "Default")
      (node (ref "U5") (pin "A9") (pinfunction "PE13_A9") (pintype "passive"))
    )
    (net (code "53") (name "/INT_I2C_SDA") (class "Default")
      (node (ref "U5") (pin "F9") (pinfunction "PE14_F9") (pintype "passive"))
    )
    (net (code "54") (name "/JTAG_TCK") (class "Default")
      (node (ref "U5") (pin "V7") (pinfunction "PA14_V7") (pintype "passive"))
    )
    (net (code "55") (name "/JTAG_TDI") (class "Default")
      (node (ref "U5") (pin "T15") (pinfunction "PA15_T15") (pintype "passive"))
    )
    (net (code "56") (name "/JTAG_TDO") (class "Default")
      (node (ref "U5") (pin "T14") (pinfunction "PB5_T14") (pintype "passive"))
    )
    (net (code "57") (name "/JTAG_TMS") (class "Default")
      (node (ref "U5") (pin "W7") (pinfunction "PA13_W7") (pintype "passive"))
    )
    (net (code "58") (name "/LED_B") (class "Default")
      (node (ref "R96") (pin "1") (pinfunction "1_1") (pintype "passive"))
      (node (ref "U5") (pin "V14") (pinfunction "PB1_V14") (pintype "passive"))
    )
    (net (code "59") (name "/LED_B_INT") (class "Default")
      (node (ref "D22") (pin "1") (pinfunction "BLUE_1") (pintype "passive"))
      (node (ref "R96") (pin "2") (pinfunction "2_2") (pintype "passive"))
    )
    (net (code "60") (name "/LED_G") (class "Default")
      (node (ref "R97") (pin "1") (pinfunction "1_1") (pintype "passive"))
      (node (ref "U5") (pin "V15") (pinfunction "PA7_V15") (pintype "passive"))
    )
    (net (code "61") (name "/LED_G_INT") (class "Default")
      (node (ref "D22") (pin "2") (pinfunction "GREEN_2") (pintype "passive"))
      (node (ref "R97") (pin "2") (pinfunction "2_2") (pintype "passive"))
    )
    (net (code "62") (name "/LED_R") (class "Default")
      (node (ref "R98") (pin "1") (pinfunction "1_1") (pintype "passive"))
      (node (ref "U5") (pin "T12") (pinfunction "PG10_T12") (pintype "passive"))
    )
    (net (code "63") (name "/LED_R_INT") (class "Default")
      (node (ref "D22") (pin "3") (pinfunction "RED_3") (pintype "passive"))
      (node (ref "R98") (pin "2") (pinfunction "2_2") (pintype "passive"))
    )
    (net (code "64") (name "/MIC_CLK") (class "Default")
      (node (ref "B15") (pin "4") (pinfunction "CLK_4") (pintype "passive"))
      (node (ref "U5") (pin "B19") (pinfunction "PE2_B19") (pintype "passive"))
    )
    (net (code "65") (name "/MIC_DATA") (class "Default")
      (node (ref "B15") (pin "1") (pinfunction "DATA_1") (pintype "passive"))
      (node (ref "U5") (pin "B16") (pinfunction "PB2_B16") (pintype "passive"))
    )
    (net (code "66") (name "/MIPI_CSI_CLK_INT_N") (class "Default")
      (node (ref "U5") (pin "V4") (pinfunction "CSI_CK_N_V4") (pintype "passive"))
      (node (ref "U6") (pin "9") (pinfunction "OUT_3-_9") (pintype "bidirectional"))
    )
    (net (code "67") (name "/MIPI_CSI_CLK_INT_P") (class "Default")
      (node (ref "U5") (pin "W4") (pinfunction "CSI_CK_P_W4") (pintype "passive"))
      (node (ref "U6") (pin "10") (pinfunction "OUT_3+_10") (pintype "bidirectional"))
    )
    (net (code "68") (name "/MIPI_CSI_CLK_N") (class "Default")
      (node (ref "U6") (pin "8") (pinfunction "IN_3-_8") (pintype "bidirectional"))
    )
    (net (code "69") (name "/MIPI_CSI_CLK_P") (class "Default")
      (node (ref "U6") (pin "7") (pinfunction "IN_3+_7") (pintype "bidirectional"))
    )
    (net (code "70") (name "/MIPI_CSI_D0_INT_N") (class "Default")
      (node (ref "U5") (pin "V5") (pinfunction "CSI_D0_N_V5") (pintype "passive"))
      (node (ref "U6") (pin "15") (pinfunction "OUT_1-_15") (pintype "bidirectional"))
    )
    (net (code "71") (name "/MIPI_CSI_D0_INT_P") (class "Default")
      (node (ref "U5") (pin "W5") (pinfunction "CSI_D0_P_W5") (pintype "passive"))
      (node (ref "U6") (pin "16") (pinfunction "OUT_1+_16") (pintype "bidirectional"))
    )
    (net (code "72") (name "/MIPI_CSI_D0_N") (class "Default")
      (node (ref "U6") (pin "2") (pinfunction "IN_1âˆ’_2") (pintype "bidirectional"))
    )
    (net (code "73") (name "/MIPI_CSI_D0_P") (class "Default")
      (node (ref "U6") (pin "1") (pinfunction "IN_1+_1") (pintype "bidirectional"))
    )
    (net (code "74") (name "/MIPI_CSI_D1_INT_N") (class "Default")
      (node (ref "U5") (pin "V3") (pinfunction "CSI_D1_N_V3") (pintype "passive"))
      (node (ref "U6") (pin "12") (pinfunction "OUT_2-_12") (pintype "bidirectional"))
    )
    (net (code "75") (name "/MIPI_CSI_D1_INT_P") (class "Default")
      (node (ref "U5") (pin "W3") (pinfunction "CSI_D1_P_W3") (pintype "passive"))
      (node (ref "U6") (pin "13") (pinfunction "OUT_2+_13") (pintype "bidirectional"))
    )
    (net (code "76") (name "/MIPI_CSI_D1_N") (class "Default")
      (node (ref "U6") (pin "5") (pinfunction "IN_2-_5") (pintype "bidirectional"))
    )
    (net (code "77") (name "/MIPI_CSI_D1_P") (class "Default")
      (node (ref "U6") (pin "4") (pinfunction "IN_2+_4") (pintype "bidirectional"))
    )
    (net (code "78") (name "/MIPI_CSI_R") (class "Default")
      (node (ref "R107") (pin "1") (pinfunction "1_1") (pintype "passive"))
      (node (ref "U5") (pin "T6") (pinfunction "CSI_REXT_T6") (pintype "passive"))
    )
    (net (code "79") (name "/ONOFF") (class "Default")
      (node (ref "C146") (pin "2") (pinfunction "2_2") (pintype "passive"))
      (node (ref "R101") (pin "2") (pinfunction "2_2") (pintype "passive"))
      (node (ref "U5") (pin "W10") (pinfunction "PA2_W10") (pintype "passive"))
    )
    (net (code "80") (name "/ONOFF_INT") (class "Default")
      (node (ref "Q5") (pin "2") (pinfunction "S_2") (pintype "bidirectional"))
      (node (ref "R101") (pin "1") (pinfunction "1_1") (pintype "passive"))
      (node (ref "R99") (pin "1") (pinfunction "1_1") (pintype "passive"))
      (node (ref "S2") (pin "2") (pinfunction "COM_2") (pintype "passive"))
      (node (ref "S2") (pin "3") (pinfunction "COM_3") (pintype "passive"))
      (node (ref "S2") (pin "4") (pinfunction "COM_4") (pintype "passive"))
    )
    (net (code "81") (name "/OTG1_R") (class "Default")
      (node (ref "R106") (pin "1") (pinfunction "1_1") (pintype "passive"))
      (node (ref "U5") (pin "A2") (pinfunction "OTG1_TRXTUNE_A2") (pintype "passive"))
    )
    (net (code "82") (name "/OTG1_VBUS") (class "Default")
      (node (ref "C147") (pin "2") (pinfunction "2_2") (pintype "passive"))
      (node (ref "R103") (pin "1") (pinfunction "1_1") (pintype "passive"))
      (node (ref "U5") (pin "B1") (pinfunction "NC_B1") (pintype "passive"))
    )
    (net (code "83") (name "/P0_MOSI") (class "Default")
      (node (ref "U5") (pin "F11") (pinfunction "PD7_F11") (pintype "passive"))
    )
    (net (code "84") (name "/P1_MISO") (class "Default")
      (node (ref "U5") (pin "A17") (pinfunction "PD11_A17") (pintype "passive"))
    )
    (net (code "85") (name "/P2_SCLK") (class "Default")
      (node (ref "U5") (pin "V8") (pinfunction "PA12_V8") (pintype "passive"))
    )
    (net (code "86") (name "/P3_SSEL") (class "Default")
      (node (ref "U5") (pin "T8") (pinfunction "PA11_T8") (pintype "passive"))
    )
    (net (code "87") (name "/P4_SCL") (class "Default")
      (node (ref "U5") (pin "T13") (pinfunction "PB10_T13") (pintype "passive"))
    )
    (net (code "88") (name "/P5_SDA") (class "Default")
      (node (ref "U5") (pin "V13") (pinfunction "PB11_V13") (pintype "passive"))
    )
    (net (code "89") (name "/P6_ADC") (class "Default")
      (node (ref "R108") (pin "2") (pinfunction "2_2") (pintype "passive"))
      (node (ref "U5") (pin "T16") (pinfunction "PG0_T16") (pintype "passive"))
    )
    (net (code "90") (name "/P6_ADC_1V8_OUT") (class "Default")
      (node (ref "U5") (pin "V10") (pinfunction "PA5_V10") (pintype "passive"))
      (node (ref "U9") (pin "1") (pinfunction "OUT_1") (pintype "passive"))
      (node (ref "U9") (pin "4") (pinfunction "IN-_4") (pintype "passive"))
    )
    (net (code "91") (name "/P7_PWM") (class "Default")
      (node (ref "U5") (pin "W11") (pinfunction "PG13_W11") (pintype "passive"))
    )
    (net (code "92") (name "/P8_PWM") (class "Default")
      (node (ref "U5") (pin "D16") (pinfunction "PD13_D16") (pintype "passive"))
    )
    (net (code "93") (name "/P9_PWM") (class "Default")
      (node (ref "U5") (pin "V11") (pinfunction "PG12_V11") (pintype "passive"))
    )
    (net (code "94") (name "/P11_WAKEUP") (class "Default")
      (node (ref "Q4") (pin "3") (pinfunction "D_3") (pintype "bidirectional"))
      (node (ref "R94") (pin "1") (pinfunction "1_1") (pintype "passive"))
    )
    (net (code "95") (name "/P12_RST_N") (class "Default")
      (node (ref "C148") (pin "1") (pinfunction "1_1") (pintype "passive"))
      (node (ref "R102") (pin "2") (pinfunction "2_2") (pintype "passive"))
      (node (ref "U5") (pin "F2") (pinfunction "NRST_F2") (pintype "passive"))
    )
    (net (code "96") (name "/P13_RX") (class "Default")
      (node (ref "U5") (pin "B11") (pinfunction "PE7_B11") (pintype "passive"))
    )
    (net (code "97") (name "/P14_TX") (class "Default")
      (node (ref "U5") (pin "A13") (pinfunction "PE8_A13") (pintype "passive"))
    )
    (net (code "98") (name "/P15_SSEL") (class "Default")
      (node (ref "U5") (pin "D8") (pinfunction "PE11_D8") (pintype "passive"))
    )
    (net (code "99") (name "/P16_SCLK") (class "Default")
      (node (ref "U5") (pin "D10") (pinfunction "PE12_D10") (pintype "passive"))
    )
    (net (code "100") (name "/P17_MISO") (class "Default")
      (node (ref "U5") (pin "D19") (pinfunction "PB6_D19") (pintype "passive"))
    )
    (net (code "101") (name "/P18_MOSI") (class "Default")
      (node (ref "U5") (pin "E16") (pinfunction "PB7_E16") (pintype "passive"))
    )
    (net (code "102") (name "/PGOOD") (class "Default")
      (node (ref "U5") (pin "G14") (pinfunction "PD9_G14") (pintype "passive"))
    )
    (net (code "103") (name "/PMIC_ONOFF") (class "Default")
      (node (ref "Q5") (pin "3") (pinfunction "D_3") (pintype "bidirectional"))
      (node (ref "R100") (pin "1") (pinfunction "1_1") (pintype "passive"))
    )
    (net (code "104") (name "/PWM_FSIN") (class "Default")
      (node (ref "U5") (pin "A10") (pinfunction "PD6_A10") (pintype "passive"))
    )
    (net (code "105") (name "/PWR_ON") (class "Default")
      (node (ref "U5") (pin "G4") (pinfunction "PWR_ON_G4") (pintype "passive"))
    )
    (net (code "106") (name "/RTC_XTALI") (class "Default")
      (node (ref "C80") (pin "1") (pinfunction "1_1") (pintype "passive"))
      (node (ref "U5") (pin "E1") (pinfunction "PC14-OSC32_IN_E1") (pintype "passive"))
      (node (ref "Y1") (pin "2") (pinfunction "2_2") (pintype "passive"))
    )
    (net (code "107") (name "/RTC_XTALO") (class "Default")
      (node (ref "C79") (pin "1") (pinfunction "1_1") (pintype "passive"))
      (node (ref "U5") (pin "D1") (pinfunction "PC15-OSC32_OUT_D1") (pintype "passive"))
      (node (ref "Y1") (pin "1") (pinfunction "1_1") (pintype "passive"))
    )
    (net (code "108") (name "/SD_CD") (class "Default")
      (node (ref "U5") (pin "A8") (pinfunction "PC6_A8") (pintype "passive"))
    )
    (net (code "109") (name "/SD_CLK") (class "Default")
      (node (ref "U5") (pin "A6") (pinfunction "PC12_A6") (pintype "passive"))
    )
    (net (code "110") (name "/SD_CMD") (class "Default")
      (node (ref "U5") (pin "D7") (pinfunction "PH2_D7") (pintype "passive"))
    )
    (net (code "111") (name "/SD_DAT0") (class "Default")
      (node (ref "U5") (pin "F6") (pinfunction "PC8_F6") (pintype "passive"))
    )
    (net (code "112") (name "/SD_DAT1") (class "Default")
      (node (ref "U5") (pin "D5") (pinfunction "PC9_D5") (pintype "passive"))
    )
    (net (code "113") (name "/SD_DAT2") (class "Default")
      (node (ref "U5") (pin "D6") (pinfunction "PC10_D6") (pintype "passive"))
    )
    (net (code "114") (name "/SD_DAT3") (class "Default")
      (node (ref "U5") (pin "B6") (pinfunction "PC11_B6") (pintype "passive"))
    )
    (net (code "115") (name "/SD_RESET") (class "Default")
      (node (ref "U5") (pin "B8") (pinfunction "PC7_B8") (pintype "passive"))
    )
    (net (code "116") (name "/SD_V_SELECT") (class "Default")
      (node (ref "U5") (pin "N1") (pinfunction "PG6_N1") (pintype "passive"))
    )
    (net (code "117") (name "/ST") (class "Default")
      (node (ref "U5") (pin "B14") (pinfunction "PD8_B14") (pintype "passive"))
    )
    (net (code "118") (name "/USB_D_N") (class "Default")
      (node (ref "U5") (pin "B3") (pinfunction "OTG1_HSDM_B3") (pintype "passive"))
    )
    (net (code "119") (name "/USB_D_P") (class "Default")
      (node (ref "U5") (pin "A3") (pinfunction "OTG1_HSDP_A3") (pintype "passive"))
    )
    (net (code "120") (name "/USER_SW") (class "Default")
      (node (ref "C25") (pin "2") (pinfunction "2_2") (pintype "passive"))
      (node (ref "R68") (pin "2") (pinfunction "2_2") (pintype "passive"))
      (node (ref "U5") (pin "M1") (pinfunction "PF4_M1") (pintype "passive"))
    )
    (net (code "121") (name "/USER_SW_INT") (class "Default")
      (node (ref "R67") (pin "1") (pinfunction "1_1") (pintype "passive"))
      (node (ref "R68") (pin "1") (pinfunction "1_1") (pintype "passive"))
      (node (ref "S1") (pin "2") (pinfunction "COM_2") (pintype "passive"))
      (node (ref "S1") (pin "3") (pinfunction "COM_3") (pintype "passive"))
      (node (ref "S1") (pin "4") (pinfunction "COM_4") (pintype "passive"))
    )
    (net (code "122") (name "/VCC_1.8V_A_GATED") (class "Default")
      (node (ref "C108") (pin "2") (pinfunction "2_2") (pintype "passive"))
      (node (ref "C128") (pin "1") (pinfunction "1_1") (pintype "passive"))
      (node (ref "C129") (pin "1") (pinfunction "1_1") (pintype "passive"))
      (node (ref "C130") (pin "2") (pinfunction "2_2") (pintype "passive"))
      (node (ref "C132") (pin "1") (pinfunction "1_1") (pintype "passive"))
      (node (ref "C134") (pin "1") (pinfunction "1_1") (pintype "passive"))
      (node (ref "C137") (pin "2") (pinfunction "2_2") (pintype "passive"))
      (node (ref "C97") (pin "1") (pinfunction "1_1") (pintype "passive"))
      (node (ref "L14") (pin "1") (pinfunction "1_1") (pintype "passive"))
      (node (ref "U5") (pin "D4") (pinfunction "VDDA18USB_D4") (pintype "passive"))
      (node (ref "U5") (pin "H1") (pinfunction "VDDA18PMU_H1") (pintype "passive"))
      (node (ref "U5") (pin "M6") (pinfunction "VDDA18PLL_M6") (pintype "passive"))
      (node (ref "U5") (pin "P6") (pinfunction "VDDA18ADC_P6") (pintype "passive"))
      (node (ref "U5") (pin "V6") (pinfunction "VDDA18CSI_V6") (pintype "passive"))
      (node (ref "U5") (pin "W2") (pinfunction "VREF+_W2") (pintype "passive"))
    )
    (net (code "123") (name "/VCC_3.3V_BAT") (class "Default")
      (node (ref "C86") (pin "1") (pinfunction "1_1") (pintype "passive"))
      (node (ref "C88") (pin "1") (pinfunction "1_1") (pintype "passive"))
      (node (ref "U4") (pin "3") (pinfunction "3_3") (pintype "passive"))
      (node (ref "U5") (pin "F1") (pinfunction "VBAT_F1") (pintype "passive"))
    )
    (net (code "124") (name "/VCC_SD_IO") (class "Default")
      (node (ref "C126") (pin "1") (pinfunction "1_1") (pintype "passive"))
      (node (ref "C127") (pin "1") (pinfunction "1_1") (pintype "passive"))
      (node (ref "C140") (pin "1") (pinfunction "1_1") (pintype "passive"))
      (node (ref "C143") (pin "1") (pinfunction "1_1") (pintype "passive"))
      (node (ref "U5") (pin "F7") (pinfunction "VDDIO4_F7") (pintype "passive"))
      (node (ref "U5") (pin "F8") (pinfunction "VDDIO4_F8") (pintype "passive"))
    )
    (net (code "125") (name "/VDD_CAP_0V8") (class "Default")
      (node (ref "C118") (pin "1") (pinfunction "1_1") (pintype "passive"))
      (node (ref "C120") (pin "1") (pinfunction "1_1") (pintype "passive"))
      (node (ref "U5") (pin "G1") (pinfunction "V08CAP_G1") (pintype "passive"))
    )
    (net (code "126") (name "/VDD_CORE_0V8") (class "Default")
      (node (ref "C111") (pin "2") (pinfunction "2_2") (pintype "passive"))
      (node (ref "C112") (pin "2") (pinfunction "2_2") (pintype "passive"))
      (node (ref "C114") (pin "2") (pinfunction "2_2") (pintype "passive"))
      (node (ref "C115") (pin "2") (pinfunction "2_2") (pintype "passive"))
      (node (ref "C116") (pin "1") (pinfunction "1_1") (pintype "passive"))
      (node (ref "C72") (pin "2") (pinfunction "2_2") (pintype "passive"))
      (node (ref "C82") (pin "2") (pinfunction "2_2") (pintype "passive"))
      (node (ref "C84") (pin "2") (pinfunction "2_2") (pintype "passive"))
      (node (ref "C85") (pin "2") (pinfunction "2_2") (pintype "passive"))
      (node (ref "C87") (pin "2") (pinfunction "2_2") (pintype "passive"))
      (node (ref "C90") (pin "2") (pinfunction "2_2") (pintype "passive"))
      (node (ref "C95") (pin "2") (pinfunction "2_2") (pintype "passive"))
      (node (ref "L5") (pin "1") (pinfunction "1_1") (pintype "passive"))
      (node (ref "U5") (pin "G2") (pinfunction "VFBSMPS_G2") (pintype "passive"))
      (node (ref "U5") (pin "P10") (pinfunction "VDDCORE_P10") (pintype "passive"))
      (node (ref "U5") (pin "P11") (pinfunction "VDDCORE_P11") (pintype "passive"))
      (node (ref "U5") (pin "P13") (pinfunction "VDDCORE_P13") (pintype "passive"))
      (node (ref "U5") (pin "P7") (pinfunction "VDDCORE_P7") (pintype "passive"))
      (node (ref "U5") (pin "P9") (pinfunction "VDDCORE_P9") (pintype "passive"))
      (node (ref "U5") (pin "W6") (pinfunction "VDDCSI_W6") (pintype "passive"))
    )
    (net (code "127") (name "/WAKEUP") (class "Default")
      (node (ref "Q4") (pin "2") (pinfunction "S_2") (pintype "bidirectional"))
      (node (ref "R95") (pin "1") (pinfunction "1_1") (pintype "passive"))
      (node (ref "U5") (pin "H4") (pinfunction "PC13_H4") (pintype "passive"))
    )
    (net (code "128") (name "/WIFI_CLK") (class "Default")
      (node (ref "U5") (pin "B10") (pinfunction "PD2_B10") (pintype "passive"))
    )
    (net (code "129") (name "/WIFI_CMD") (class "Default")
      (node (ref "U5") (pin "V12") (pinfunction "PA0_V12") (pintype "passive"))
    )
    (net (code "130") (name "/WIFI_D0") (class "Default")
      (node (ref "U5") (pin "D15") (pinfunction "PB8_D15") (pintype "passive"))
    )
    (net (code "131") (name "/WIFI_D1") (class "Default")
      (node (ref "U5") (pin "V17") (pinfunction "PG8_V17") (pintype "passive"))
    )
    (net (code "132") (name "/WIFI_D2") (class "Default")
      (node (ref "U5") (pin "B15") (pinfunction "PB9_B15") (pintype "passive"))
    )
    (net (code "133") (name "/WIFI_D3") (class "Default")
      (node (ref "U5") (pin "W15") (pinfunction "PB4_W15") (pintype "passive"))
    )
    (net (code "134") (name "/WIFI_I2S_SCLK") (class "Default")
      (node (ref "U5") (pin "A16") (pinfunction "PB13_A16") (pintype "passive"))
    )
    (net (code "135") (name "/WIFI_I2S_SDI") (class "Default")
      (node (ref "R104") (pin "1") (pinfunction "1_1") (pintype "passive"))
      (node (ref "U5") (pin "T10") (pinfunction "PA6_T10") (pintype "passive"))
    )
    (net (code "136") (name "/WIFI_I2S_SDO") (class "Default")
      (node (ref "U5") (pin "T7") (pinfunction "PG14_T7") (pintype "passive"))
    )
    (net (code "137") (name "/WIFI_I2S_WS") (class "Default")
      (node (ref "U5") (pin "A14") (pinfunction "PB15_A14") (pintype "passive"))
    )
    (net (code "138") (name "/WL_H_WAKE") (class "Default")
      (node (ref "U5") (pin "C17") (pinfunction "PB14_C17") (pintype "passive"))
    )
    (net (code "139") (name "/WL_REG_ON") (class "Default")
      (node (ref "U5") (pin "W13") (pinfunction "PB12_W13") (pintype "passive"))
    )
    (net (code "140") (name "/XSPIM_P1_CLK_P") (class "Default")
      (node (ref "U5") (pin "J18") (pinfunction "PO4_J18") (pintype "passive"))
    )
    (net (code "141") (name "/XSPIM_P1_DQS0") (class "Default")
      (node (ref "U5") (pin "G18") (pinfunction "PO2_G18") (pintype "passive"))
    )
    (net (code "142") (name "/XSPIM_P1_DQS1") (class "Default")
      (node (ref "U5") (pin "E18") (pinfunction "PO3_E18") (pintype "passive"))
    )
    (net (code "143") (name "/XSPIM_P1_IO0") (class "Default")
      (node (ref "U5") (pin "H18") (pinfunction "PP0_H18") (pintype "passive"))
    )
    (net (code "144") (name "/XSPIM_P1_IO1") (class "Default")
      (node (ref "U5") (pin "F18") (pinfunction "PP1_F18") (pintype "passive"))
    )
    (net (code "145") (name "/XSPIM_P1_IO2") (class "Default")
      (node (ref "U5") (pin "K18") (pinfunction "PP2_K18") (pintype "passive"))
    )
    (net (code "146") (name "/XSPIM_P1_IO3") (class "Default")
      (node (ref "U5") (pin "K19") (pinfunction "PP3_K19") (pintype "passive"))
    )
    (net (code "147") (name "/XSPIM_P1_IO4") (class "Default")
      (node (ref "U5") (pin "L19") (pinfunction "PP4_L19") (pintype "passive"))
    )
    (net (code "148") (name "/XSPIM_P1_IO5") (class "Default")
      (node (ref "U5") (pin "J19") (pinfunction "PP5_J19") (pintype "passive"))
    )
    (net (code "149") (name "/XSPIM_P1_IO6") (class "Default")
      (node (ref "U5") (pin "H19") (pinfunction "PP6_H19") (pintype "passive"))
    )
    (net (code "150") (name "/XSPIM_P1_IO7") (class "Default")
      (node (ref "U5") (pin "G19") (pinfunction "PP7_G19") (pintype "passive"))
    )
    (net (code "151") (name "/XSPIM_P1_IO8") (class "Default")
      (node (ref "U5") (pin "F19") (pinfunction "PP8_F19") (pintype "passive"))
    )
    (net (code "152") (name "/XSPIM_P1_IO9") (class "Default")
      (node (ref "U5") (pin "E19") (pinfunction "PP9_E19") (pintype "passive"))
    )
    (net (code "153") (name "/XSPIM_P1_IO10") (class "Default")
      (node (ref "U5") (pin "D18") (pinfunction "PP10_D18") (pintype "passive"))
    )
    (net (code "154") (name "/XSPIM_P1_IO11") (class "Default")
      (node (ref "U5") (pin "N19") (pinfunction "PP11_N19") (pintype "passive"))
    )
    (net (code "155") (name "/XSPIM_P1_IO12") (class "Default")
      (node (ref "U5") (pin "N18") (pinfunction "PP12_N18") (pintype "passive"))
    )
    (net (code "156") (name "/XSPIM_P1_IO13") (class "Default")
      (node (ref "U5") (pin "M19") (pinfunction "PP13_M19") (pintype "passive"))
    )
    (net (code "157") (name "/XSPIM_P1_IO14") (class "Default")
      (node (ref "U5") (pin "M18") (pinfunction "PP14_M18") (pintype "passive"))
    )
    (net (code "158") (name "/XSPIM_P1_IO15") (class "Default")
      (node (ref "U5") (pin "L18") (pinfunction "PP15_L18") (pintype "passive"))
    )
    (net (code "159") (name "/XSPIM_P1_NCS1") (class "Default")
      (node (ref "U5") (pin "F16") (pinfunction "PO0_F16") (pintype "passive"))
    )
    (net (code "160") (name "/XSPIM_P2_CLK_N") (class "Default")
      (node (ref "U5") (pin "R16") (pinfunction "PN7_R16") (pintype "passive"))
    )
    (net (code "161") (name "/XSPIM_P2_CLK_P") (class "Default")
      (node (ref "U5") (pin "U19") (pinfunction "PN6_U19") (pintype "passive"))
    )
    (net (code "162") (name "/XSPIM_P2_DQS0") (class "Default")
      (node (ref "U5") (pin "R19") (pinfunction "PN0_R19") (pintype "passive"))
    )
    (net (code "163") (name "/XSPIM_P2_INT#") (class "Default")
      (node (ref "U5") (pin "W18") (pinfunction "PN12_W18") (pintype "passive"))
    )
    (net (code "164") (name "/XSPIM_P2_IO0") (class "Default")
      (node (ref "U5") (pin "T19") (pinfunction "PN2_T19") (pintype "passive"))
    )
    (net (code "165") (name "/XSPIM_P2_IO1") (class "Default")
      (node (ref "U5") (pin "P19") (pinfunction "PN3_P19") (pintype "passive"))
    )
    (net (code "166") (name "/XSPIM_P2_IO2") (class "Default")
      (node (ref "U5") (pin "V19") (pinfunction "PN4_V19") (pintype "passive"))
    )
    (net (code "167") (name "/XSPIM_P2_IO3") (class "Default")
      (node (ref "U5") (pin "U18") (pinfunction "PN5_U18") (pintype "passive"))
    )
    (net (code "168") (name "/XSPIM_P2_IO4") (class "Default")
      (node (ref "U5") (pin "V18") (pinfunction "PN8_V18") (pintype "passive"))
    )
    (net (code "169") (name "/XSPIM_P2_IO5") (class "Default")
      (node (ref "U5") (pin "T18") (pinfunction "PN9_T18") (pintype "passive"))
    )
    (net (code "170") (name "/XSPIM_P2_IO6") (class "Default")
      (node (ref "U5") (pin "R18") (pinfunction "PN10_R18") (pintype "passive"))
    )
    (net (code "171") (name "/XSPIM_P2_IO7") (class "Default")
      (node (ref "U5") (pin "P18") (pinfunction "PN11_P18") (pintype "passive"))
    )
    (net (code "172") (name "/XSPIM_P2_NCS1") (class "Default")
      (node (ref "U5") (pin "P16") (pinfunction "PN1_P16") (pintype "passive"))
    )
    (net (code "173") (name "/XTALI") (class "Default")
      (node (ref "C106") (pin "1") (pinfunction "1_1") (pintype "passive"))
      (node (ref "U5") (pin "A5") (pinfunction "PH0-OSC_IN_A5") (pintype "passive"))
      (node (ref "Y2") (pin "3") (pinfunction "CRYSTAL_2_3") (pintype "bidirectional"))
    )
    (net (code "174") (name "/XTALO") (class "Default")
      (node (ref "C105") (pin "1") (pinfunction "1_1") (pintype "passive"))
      (node (ref "U5") (pin "B5") (pinfunction "PH1-OSC_OUT_B5") (pintype "passive"))
      (node (ref "Y2") (pin "1") (pinfunction "CRYSTAL_1_1") (pintype "bidirectional"))
    )
    (net (code "175") (name "GND") (class "Default")
      (node (ref "B15") (pin "2") (pinfunction "SELECT_2") (pintype "passive"))
      (node (ref "B15") (pin "3") (pinfunction "GND_3") (pintype "passive"))
      (node (ref "C100") (pin "2") (pinfunction "2_2") (pintype "passive"))
      (node (ref "C101") (pin "2") (pinfunction "2_2") (pintype "passive"))
      (node (ref "C102") (pin "2") (pinfunction "2_2") (pintype "passive"))
      (node (ref "C103") (pin "2") (pinfunction "2_2") (pintype "passive"))
      (node (ref "C104") (pin "2") (pinfunction "2_2") (pintype "passive"))
      (node (ref "C105") (pin "2") (pinfunction "2_2") (pintype "passive"))
      (node (ref "C106") (pin "2") (pinfunction "2_2") (pintype "passive"))
      (node (ref "C107") (pin "1") (pinfunction "1_1") (pintype "passive"))
      (node (ref "C108") (pin "1") (pinfunction "1_1") (pintype "passive"))
      (node (ref "C109") (pin "1") (pinfunction "1_1") (pintype "passive"))
      (node (ref "C111") (pin "1") (pinfunction "1_1") (pintype "passive"))
      (node (ref "C112") (pin "1") (pinfunction "1_1") (pintype "passive"))
      (node (ref "C114") (pin "1") (pinfunction "1_1") (pintype "passive"))
      (node (ref "C115") (pin "1") (pinfunction "1_1") (pintype "passive"))
      (node (ref "C116") (pin "2") (pinfunction "2_2") (pintype "passive"))
      (node (ref "C118") (pin "2") (pinfunction "2_2") (pintype "passive"))
      (node (ref "C119") (pin "2") (pinfunction "2_2") (pintype "passive"))
      (node (ref "C120") (pin "2") (pinfunction "2_2") (pintype "passive"))
      (node (ref "C121") (pin "2") (pinfunction "2_2") (pintype "passive"))
      (node (ref "C122") (pin "2") (pinfunction "2_2") (pintype "passive"))
      (node (ref "C123") (pin "2") (pinfunction "2_2") (pintype "passive"))
      (node (ref "C124") (pin "2") (pinfunction "2_2") (pintype "passive"))
      (node (ref "C125") (pin "2") (pinfunction "2_2") (pintype "passive"))
      (node (ref "C126") (pin "2") (pinfunction "2_2") (pintype "passive"))
      (node (ref "C127") (pin "2") (pinfunction "2_2") (pintype "passive"))
      (node (ref "C128") (pin "2") (pinfunction "2_2") (pintype "passive"))
      (node (ref "C129") (pin "2") (pinfunction "2_2") (pintype "passive"))
      (node (ref "C13") (pin "2") (pinfunction "2_2") (pintype "passive"))
      (node (ref "C130") (pin "1") (pinfunction "1_1") (pintype "passive"))
      (node (ref "C132") (pin "2") (pinfunction "2_2") (pintype "passive"))
      (node (ref "C134") (pin "2") (pinfunction "2_2") (pintype "passive"))
      (node (ref "C136") (pin "2") (pinfunction "2_2") (pintype "passive"))
      (node (ref "C137") (pin "1") (pinfunction "1_1") (pintype "passive"))
      (node (ref "C138") (pin "1") (pinfunction "1_1") (pintype "passive"))
      (node (ref "C14") (pin "2") (pinfunction "2_2") (pintype "passive"))
      (node (ref "C140") (pin "2") (pinfunction "2_2") (pintype "passive"))
      (node (ref "C142") (pin "1") (pinfunction "1_1") (pintype "passive"))
      (node (ref "C143") (pin "2") (pinfunction "2_2") (pintype "passive"))
      (node (ref "C144") (pin "2") (pinfunction "2_2") (pintype "passive"))
      (node (ref "C146") (pin "1") (pinfunction "1_1") (pintype "passive"))
      (node (ref "C147") (pin "1") (pinfunction "1_1") (pintype "passive"))
      (node (ref "C148") (pin "2") (pinfunction "2_2") (pintype "passive"))
      (node (ref "C149") (pin "1") (pinfunction "1_1") (pintype "passive"))
      (node (ref "C15") (pin "2") (pinfunction "2_2") (pintype "passive"))
      (node (ref "C25") (pin "1") (pinfunction "1_1") (pintype "passive"))
      (node (ref "C70") (pin "1") (pinfunction "1_1") (pintype "passive"))
      (node (ref "C71") (pin "2") (pinfunction "2_2") (pintype "passive"))
      (node (ref "C72") (pin "1") (pinfunction "1_1") (pintype "passive"))
      (node (ref "C73") (pin "2") (pinfunction "2_2") (pintype "passive"))
      (node (ref "C79") (pin "2") (pinfunction "2_2") (pintype "passive"))
      (node (ref "C80") (pin "2") (pinfunction "2_2") (pintype "passive"))
      (node (ref "C81") (pin "2") (pinfunction "2_2") (pintype "passive"))
      (node (ref "C82") (pin "1") (pinfunction "1_1") (pintype "passive"))
      (node (ref "C83") (pin "2") (pinfunction "2_2") (pintype "passive"))
      (node (ref "C84") (pin "1") (pinfunction "1_1") (pintype "passive"))
      (node (ref "C85") (pin "1") (pinfunction "1_1") (pintype "passive"))
      (node (ref "C86") (pin "2") (pinfunction "2_2") (pintype "passive"))
      (node (ref "C87") (pin "1") (pinfunction "1_1") (pintype "passive"))
      (node (ref "C88") (pin "2") (pinfunction "2_2") (pintype "passive"))
      (node (ref "C89") (pin "2") (pinfunction "2_2") (pintype "passive"))
      (node (ref "C90") (pin "1") (pinfunction "1_1") (pintype "passive"))
      (node (ref "C94") (pin "2") (pinfunction "2_2") (pintype "passive"))
      (node (ref "C95") (pin "1") (pinfunction "1_1") (pintype "passive"))
      (node (ref "C96") (pin "1") (pinfunction "1_1") (pintype "passive"))
      (node (ref "C97") (pin "2") (pinfunction "2_2") (pintype "passive"))
      (node (ref "R104") (pin "2") (pinfunction "2_2") (pintype "passive"))
      (node (ref "R105") (pin "2") (pinfunction "2_2") (pintype "passive"))
      (node (ref "R106") (pin "2") (pinfunction "2_2") (pintype "passive"))
      (node (ref "R107") (pin "2") (pinfunction "2_2") (pintype "passive"))
      (node (ref "R110") (pin "2") (pinfunction "2_2") (pintype "passive"))
      (node (ref "R111") (pin "2") (pinfunction "2_2") (pintype "passive"))
      (node (ref "R112") (pin "2") (pinfunction "2_2") (pintype "passive"))
      (node (ref "S1") (pin "1") (pinfunction "NO_1") (pintype "passive"))
      (node (ref "S1") (pin "5") (pinfunction "NO_5") (pintype "passive"))
      (node (ref "S2") (pin "1") (pinfunction "NO_1") (pintype "passive"))
      (node (ref "S2") (pin "5") (pinfunction "NO_5") (pintype "passive"))
      (node (ref "TP2") (pin "1") (pinfunction "1_1") (pintype "passive"))
      (node (ref "U10") (pin "2") (pinfunction "GND_2") (pintype "passive"))
      (node (ref "U5") (pin "A19") (pinfunction "VSS_A19") (pintype "passive"))
      (node (ref "U5") (pin "F12") (pinfunction "VSS_F12") (pintype "passive"))
      (node (ref "U5") (pin "G6") (pinfunction "VSSAON_G6") (pintype "passive"))
      (node (ref "U5") (pin "H14") (pinfunction "VSS_H14") (pintype "passive"))
      (node (ref "U5") (pin "H2") (pinfunction "VSSAPMU_H2") (pintype "passive"))
      (node (ref "U5") (pin "J1") (pinfunction "VSSSMPS_J1") (pintype "passive"))
      (node (ref "U5") (pin "J2") (pinfunction "VSSSMPS_J2") (pintype "passive"))
      (node (ref "U5") (pin "J3") (pinfunction "VSSSMPS_J3") (pintype "passive"))
      (node (ref "U5") (pin "J4") (pinfunction "VSSSMPS_J4") (pintype "passive"))
      (node (ref "U5") (pin "J5") (pinfunction "VSSSMPS_J5") (pintype "passive"))
      (node (ref "U5") (pin "N16") (pinfunction "VSS_N16") (pintype "passive"))
      (node (ref "U5") (pin "N6") (pinfunction "VSSA_N6") (pintype "passive"))
      (node (ref "U5") (pin "P12") (pinfunction "VSS_P12") (pintype "passive"))
      (node (ref "U5") (pin "P14") (pinfunction "VSS_P14") (pintype "passive"))
      (node (ref "U5") (pin "P8") (pinfunction "VSS_P8") (pintype "passive"))
      (node (ref "U5") (pin "V2") (pinfunction "VREF-_V2") (pintype "passive"))
      (node (ref "U5") (pin "W1") (pinfunction "VSS_W1") (pintype "passive"))
      (node (ref "U5") (pin "W19") (pinfunction "VSS_W19") (pintype "passive"))
      (node (ref "U6") (pin "3_14") (pinfunction "VN_3_14") (pintype "power_in"))
      (node (ref "U6") (pin "6_11") (pinfunction "VN_6_11") (pintype "power_in"))
      (node (ref "U9") (pin "2") (pinfunction "GND_2") (pintype "passive"))
      (node (ref "Y2") (pin "2") (pinfunction "NC_1_2") (pintype "bidirectional"))
      (node (ref "Y2") (pin "4") (pinfunction "NC_2_4") (pintype "bidirectional"))
    )
    (net (code "176") (name "Net-(L5-Pad2)") (class "Default")
      (node (ref "L5") (pin "2") (pinfunction "2_2") (pintype "passive"))
      (node (ref "U5") (pin "K1") (pinfunction "VLXSMPS_K1") (pintype "passive"))
      (node (ref "U5") (pin "K2") (pinfunction "VLXSMPS_K2") (pintype "passive"))
      (node (ref "U5") (pin "K3") (pinfunction "VLXSMPS_K3") (pintype "passive"))
      (node (ref "U5") (pin "K4") (pinfunction "VLXSMPS_K4") (pintype "passive"))
      (node (ref "U5") (pin "K5") (pinfunction "VLXSMPS_K5") (pintype "passive"))
    )
    (net (code "177") (name "Net-(U5B-OTG2_TRXTUNE)") (class "Default")
      (node (ref "R112") (pin "1") (pinfunction "1_1") (pintype "passive"))
      (node (ref "U5") (pin "E2") (pinfunction "OTG2_TRXTUNE_E2") (pintype "passive"))
    )
    (net (code "178") (name "Net-(U9-IN+)") (class "Default")
      (node (ref "D9") (pin "2") (pinfunction "2_2") (pintype "passive"))
      (node (ref "R108") (pin "1") (pinfunction "1_1") (pintype "passive"))
      (node (ref "R110") (pin "1") (pinfunction "1_1") (pintype "passive"))
      (node (ref "U9") (pin "3") (pinfunction "IN+_3") (pintype "passive"))
    )
    (net (code "179") (name "Net-(U10-IN+)") (class "Default")
      (node (ref "D11") (pin "2") (pinfunction "2_2") (pintype "passive"))
      (node (ref "R109") (pin "1") (pinfunction "1_1") (pintype "passive"))
      (node (ref "R111") (pin "1") (pinfunction "1_1") (pintype "passive"))
      (node (ref "U10") (pin "3") (pinfunction "IN+_3") (pintype "passive"))
    )
    (net (code "180") (name "RAW") (class "Default")
      (node (ref "R100") (pin "2") (pinfunction "2_2") (pintype "passive"))
      (node (ref "R94") (pin "2") (pinfunction "2_2") (pintype "passive"))
    )
    (net (code "181") (name "VBUS") (class "Default")
      (node (ref "R103") (pin "2") (pinfunction "2_2") (pintype "passive"))
    )
    (net (code "182") (name "VCC_1.8V") (class "Default")
      (node (ref "L13") (pin "2") (pinfunction "2_2") (pintype "passive"))
    )
    (net (code "183") (name "VCC_1.8V_A") (class "Default")
      (node (ref "C107") (pin "2") (pinfunction "2_2") (pintype "passive"))
      (node (ref "C136") (pin "1") (pinfunction "1_1") (pintype "passive"))
      (node (ref "C138") (pin "2") (pinfunction "2_2") (pintype "passive"))
      (node (ref "C149") (pin "2") (pinfunction "2_2") (pintype "passive"))
      (node (ref "L13") (pin "1") (pinfunction "1_1") (pintype "passive"))
      (node (ref "U5") (pin "A1") (pinfunction "PDR_ON_A1") (pintype "passive"))
      (node (ref "U5") (pin "H6") (pinfunction "VDDA18AON_H6") (pintype "passive"))
    )
    (net (code "184") (name "VCC_1.8V_GATED") (class "Default")
      (node (ref "C100") (pin "1") (pinfunction "1_1") (pintype "passive"))
      (node (ref "C101") (pin "1") (pinfunction "1_1") (pintype "passive"))
      (node (ref "C102") (pin "1") (pinfunction "1_1") (pintype "passive"))
      (node (ref "C103") (pin "1") (pinfunction "1_1") (pintype "passive"))
      (node (ref "C104") (pin "1") (pinfunction "1_1") (pintype "passive"))
      (node (ref "C109") (pin "2") (pinfunction "2_2") (pintype "passive"))
      (node (ref "C119") (pin "1") (pinfunction "1_1") (pintype "passive"))
      (node (ref "C121") (pin "1") (pinfunction "1_1") (pintype "passive"))
      (node (ref "C122") (pin "1") (pinfunction "1_1") (pintype "passive"))
      (node (ref "C123") (pin "1") (pinfunction "1_1") (pintype "passive"))
      (node (ref "C124") (pin "1") (pinfunction "1_1") (pintype "passive"))
      (node (ref "C125") (pin "1") (pinfunction "1_1") (pintype "passive"))
      (node (ref "C142") (pin "2") (pinfunction "2_2") (pintype "passive"))
      (node (ref "C144") (pin "1") (pinfunction "1_1") (pintype "passive"))
      (node (ref "C96") (pin "2") (pinfunction "2_2") (pintype "passive"))
      (node (ref "D11") (pin "1") (pinfunction "1_1") (pintype "passive"))
      (node (ref "D9") (pin "1") (pinfunction "1_1") (pintype "passive"))
      (node (ref "L14") (pin "2") (pinfunction "2_2") (pintype "passive"))
      (node (ref "U5") (pin "H16") (pinfunction "VDDIO2_H16") (pintype "passive"))
      (node (ref "U5") (pin "J16") (pinfunction "VDDIO2_J16") (pintype "passive"))
      (node (ref "U5") (pin "K16") (pinfunction "VDDIO2_K16") (pintype "passive"))
      (node (ref "U5") (pin "L1") (pinfunction "VDDSMPS_L1") (pintype "passive"))
      (node (ref "U5") (pin "L16") (pinfunction "VDDIO2_L16") (pintype "passive"))
      (node (ref "U5") (pin "L2") (pinfunction "VDDSMPS_L2") (pintype "passive"))
      (node (ref "U5") (pin "L3") (pinfunction "VDDSMPS_L3") (pintype "passive"))
      (node (ref "U5") (pin "L4") (pinfunction "VDDSMPS_L4") (pintype "passive"))
      (node (ref "U5") (pin "L5") (pinfunction "VDDSMPS_L5") (pintype "passive"))
      (node (ref "U5") (pin "M14") (pinfunction "VDDIO3_M14") (pintype "passive"))
      (node (ref "U5") (pin "M16") (pinfunction "VDDIO3_M16") (pintype "passive"))
    )
    (net (code "185") (name "VCC_3.3V") (class "Default")
      (node (ref "C70") (pin "2") (pinfunction "2_2") (pintype "passive"))
      (node (ref "C71") (pin "1") (pinfunction "1_1") (pintype "passive"))
      (node (ref "C73") (pin "1") (pinfunction "1_1") (pintype "passive"))
      (node (ref "C81") (pin "1") (pinfunction "1_1") (pintype "passive"))
      (node (ref "C83") (pin "1") (pinfunction "1_1") (pintype "passive"))
      (node (ref "Q4") (pin "1") (pinfunction "G_1") (pintype "bidirectional"))
      (node (ref "Q5") (pin "1") (pinfunction "G_1") (pintype "bidirectional"))
      (node (ref "R102") (pin "1") (pinfunction "1_1") (pintype "passive"))
      (node (ref "R95") (pin "2") (pinfunction "2_2") (pintype "passive"))
      (node (ref "R99") (pin "2") (pinfunction "2_2") (pintype "passive"))
      (node (ref "U4") (pin "1") (pinfunction "1_1") (pintype "passive"))
      (node (ref "U5") (pin "J14") (pinfunction "VDD_J14") (pintype "passive"))
      (node (ref "U5") (pin "K14") (pinfunction "VDD_K14") (pintype "passive"))
      (node (ref "U5") (pin "L14") (pinfunction "VDD_L14") (pintype "passive"))
    )
    (net (code "186") (name "VCC_3.3V_GATED") (class "Default")
      (node (ref "B15") (pin "5") (pinfunction "VDD_5") (pintype "passive"))
      (node (ref "C13") (pin "1") (pinfunction "1_1") (pintype "passive"))
      (node (ref "C14") (pin "1") (pinfunction "1_1") (pintype "passive"))
      (node (ref "C15") (pin "1") (pinfunction "1_1") (pintype "passive"))
      (node (ref "C89") (pin "1") (pinfunction "1_1") (pintype "passive"))
      (node (ref "C94") (pin "1") (pinfunction "1_1") (pintype "passive"))
      (node (ref "D22") (pin "4") (pinfunction "ANODE_4") (pintype "passive"))
      (node (ref "R67") (pin "2") (pinfunction "2_2") (pintype "passive"))
      (node (ref "U10") (pin "5") (pinfunction "VDD_5") (pintype "passive"))
      (node (ref "U5") (pin "C3") (pinfunction "VDD33USB_C3") (pintype "passive"))
      (node (ref "U9") (pin "5") (pinfunction "VDD_5") (pintype "passive"))
    )
    (net (code "187") (name "unconnected-(U5A-PC1-PadA7)") (class "Default")
      (node (ref "U5") (pin "A7") (pinfunction "PC1_A7") (pintype "passive+no_connect"))
    )
    (net (code "188") (name "unconnected-(U5A-PH9-PadB7)") (class "Default")
      (node (ref "U5") (pin "B7") (pinfunction "PH9_B7") (pintype "passive+no_connect"))
    )
    (net (code "189") (name "unconnected-(U5A-PO1-PadN14)") (class "Default")
      (node (ref "U5") (pin "N14") (pinfunction "PO1_N14") (pintype "passive+no_connect"))
    )
    (net (code "190") (name "unconnected-(U5A-PO5-PadG16)") (class "Default")
      (node (ref "U5") (pin "G16") (pinfunction "PO5_G16") (pintype "passive+no_connect"))
    )
    (net (code "191") (name "unconnected-(U5B-NC-PadD2)") (class "Default")
      (node (ref "U5") (pin "D2") (pinfunction "NC_D2") (pintype "passive+no_connect"))
    )
    (net (code "192") (name "unconnected-(U5B-OTG1_ID-PadA4)") (class "Default")
      (node (ref "U5") (pin "A4") (pinfunction "OTG1_ID_A4") (pintype "passive+no_connect"))
    )
    (net (code "193") (name "unconnected-(U5B-OTG2_HSDM-PadC2)") (class "Default")
      (node (ref "U5") (pin "C2") (pinfunction "OTG2_HSDM_C2") (pintype "passive+no_connect"))
    )
    (net (code "194") (name "unconnected-(U5B-OTG2_HSDP-PadC1)") (class "Default")
      (node (ref "U5") (pin "C1") (pinfunction "OTG2_HSDP_C1") (pintype "passive+no_connect"))
    )
    (net (code "195") (name "unconnected-(U5B-OTG2_ID-PadE4)") (class "Default")
      (node (ref "U5") (pin "E4") (pinfunction "OTG2_ID_E4") (pintype "passive+no_connect"))
    )
    (net (code "196") (name "unconnected-(U5B-UCPD1_CC1-PadA4)") (class "Default")
      (node (ref "U5") (pin "A4") (pinfunction "UCPD1_CC1_A4") (pintype "passive+no_connect"))
    )
    (net (code "197") (name "unconnected-(U5B-UCPD1_CC2-PadB4)") (class "Default")
      (node (ref "U5") (pin "B4") (pinfunction "UCPD1_CC2_B4") (pintype "passive+no_connect"))
    )
  )
)
